# CSWrite3_0_1_V0_51.net
KiCad netlist of a schematic drawn in Altium Designer
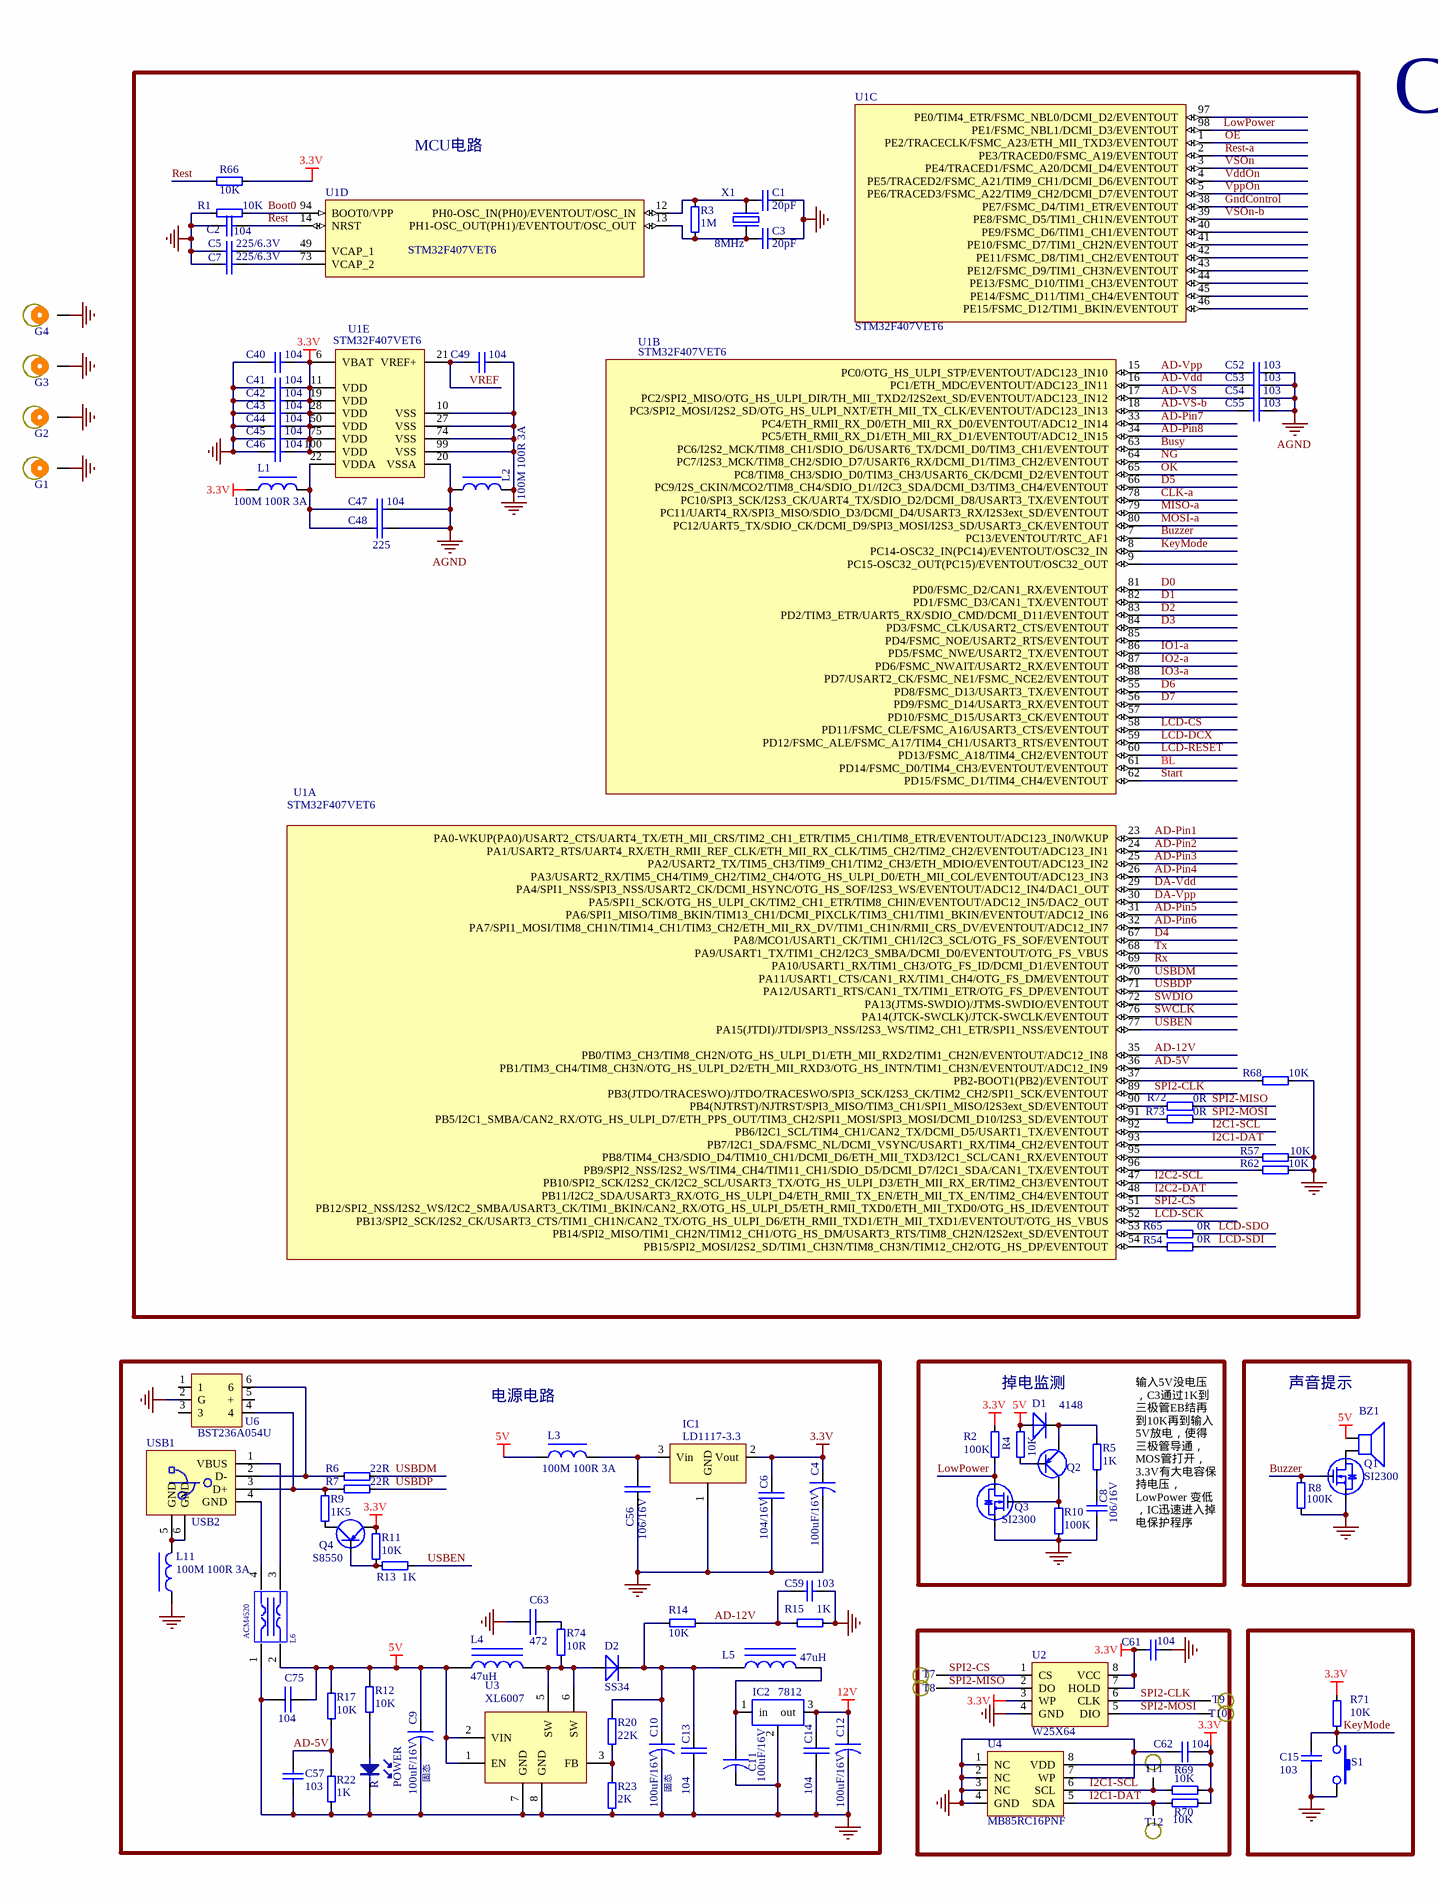
[diagram p0: CSWrite3.0.1 V0.51.SchDoc, left]
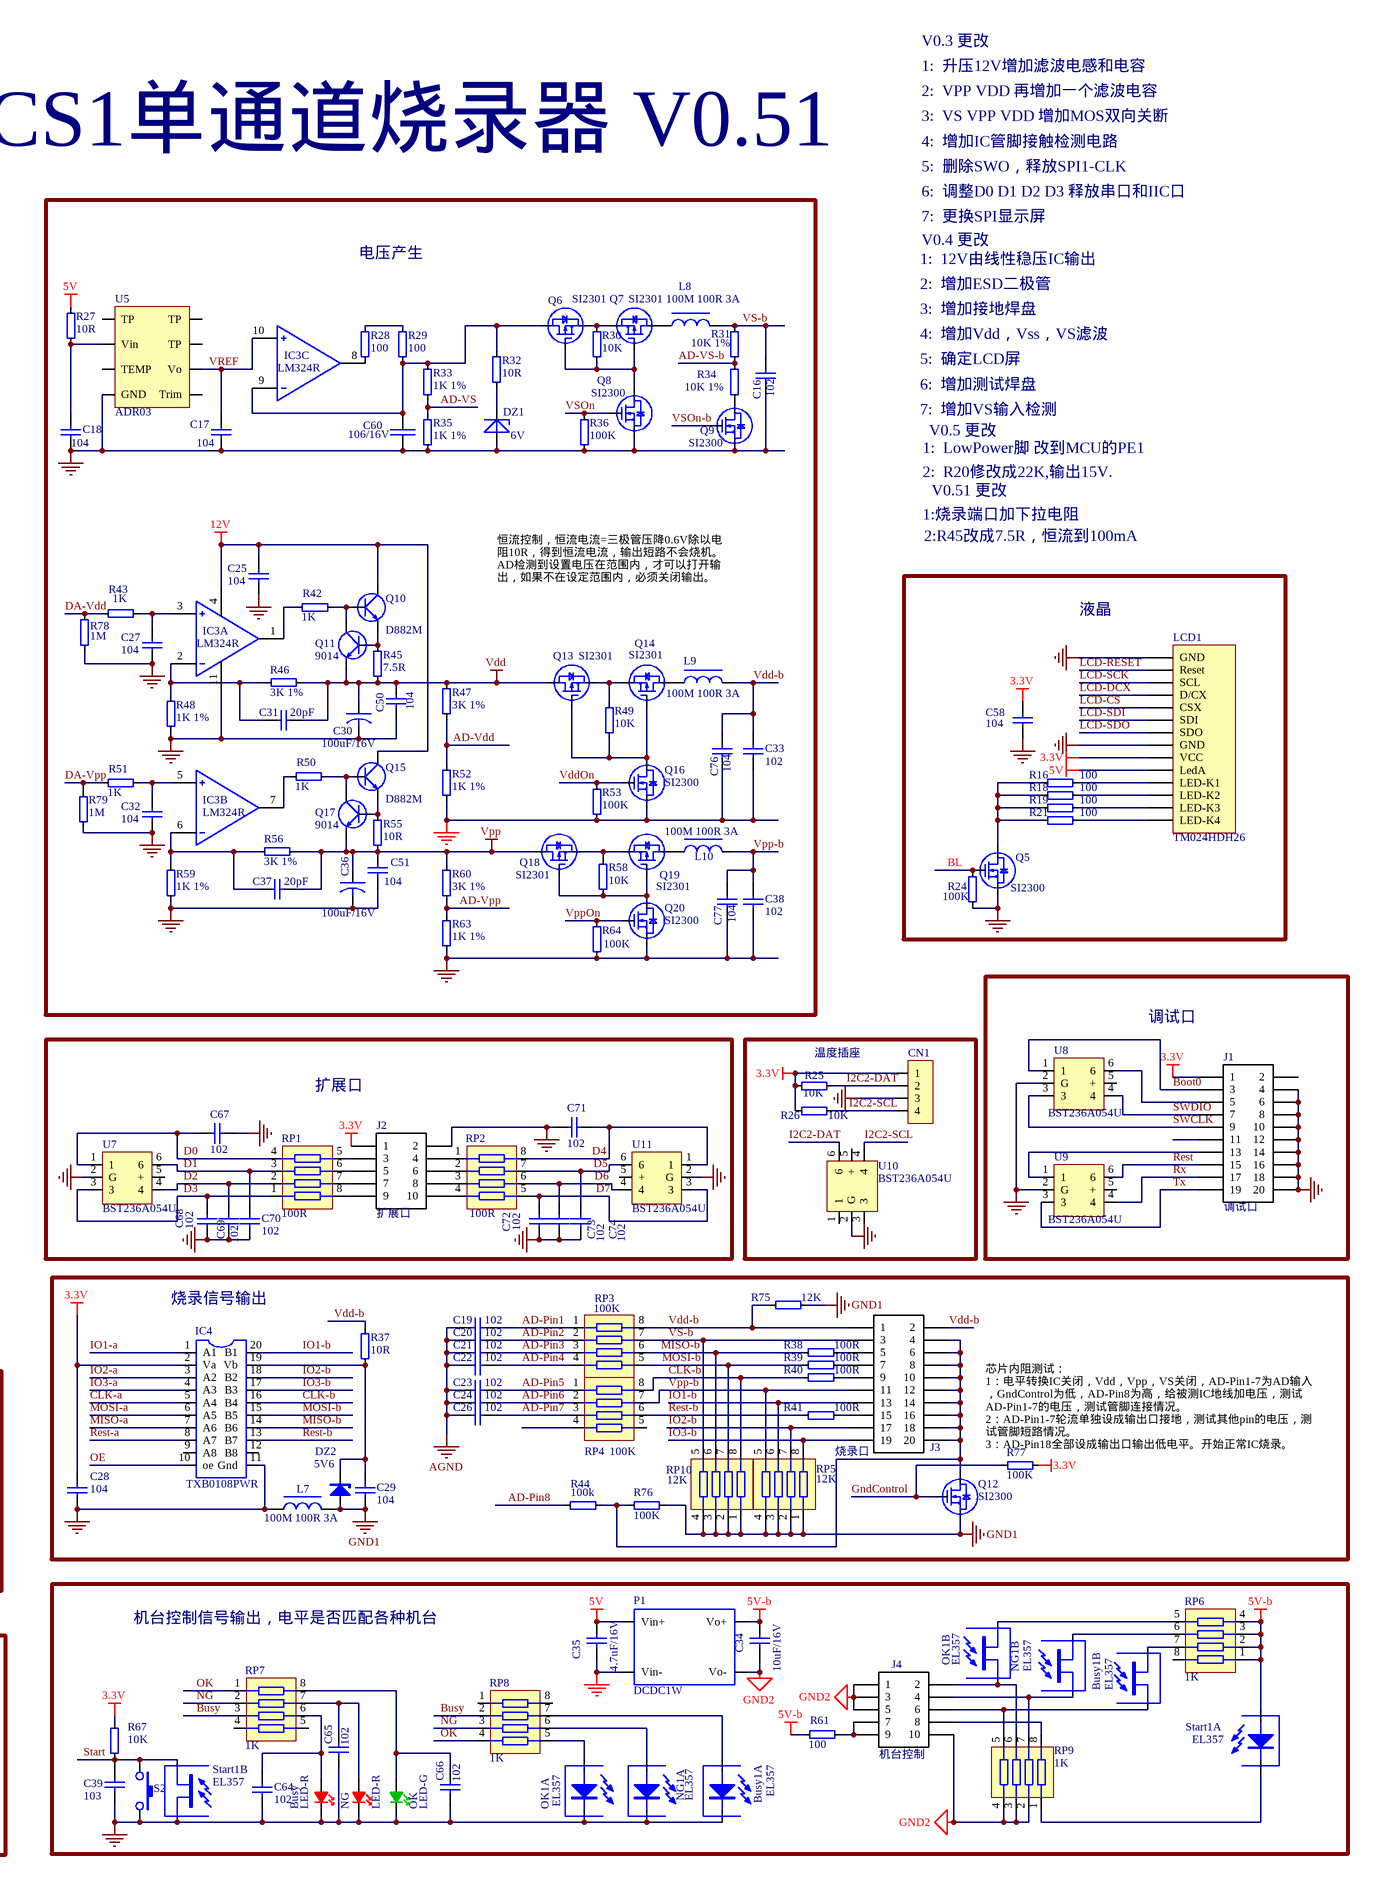
[diagram p1: CSWrite3.0.1 V0.51.SchDoc, right]

(export (version "E")
  (design (tool "Eeschema 10.0.6"))
  (components
    (comp (ref "Busy") (value "LED-R") (footprint "LED05") (libsource (lib "DCRL_W") (part "LEDR")))
    (comp (ref "Busy1") (value "EL357") (footprint "SOP-4") (libsource (lib "ASD9084-负载 V1") (part "MOS光耦")))
    (comp (ref "BZ1") (value "BUZZER") (footprint "FMQ-9*5.5") (libsource (lib "DCRL") (part "Speaker")))
    (comp (ref "C1")
      (value "20pF")
      (footprint "0603C")
      (description "无极电容")
      (libsource (lib "DCRL") (part "CAP"))
    )
    (comp (ref "C2")
      (value "104")
      (footprint "0603C")
      (description "无极电容")
      (libsource (lib "DCRL") (part "CAP"))
    )
    (comp (ref "C3")
      (value "20pF")
      (footprint "0603C")
      (description "无极电容")
      (libsource (lib "DCRL") (part "CAP"))
    )
    (comp (ref "C4")
      (value "100uF/16V")
      (footprint "CAP-B")
      (description "Capacitor")
      (libsource (lib "DCRL") (part "CAPACITOR"))
    )
    (comp (ref "C5")
      (value "225/6.3V")
      (footprint "0603C")
      (description "无极电容")
      (libsource (lib "DCRL") (part "CAP"))
    )
    (comp (ref "C6")
      (value "104/16V")
      (footprint "0603C")
      (description "无极电容")
      (libsource (lib "*") (part "CAP"))
    )
    (comp (ref "C7")
      (value "225/6.3V")
      (footprint "0603C")
      (description "无极电容")
      (libsource (lib "DCRL") (part "CAP"))
    )
    (comp (ref "C8")
      (value "106/16V")
      (footprint "0603C")
      (description "无极电容")
      (libsource (lib "DCRL") (part "CAP"))
    )
    (comp (ref "C9")
      (value "100uF/16V")
      (footprint "CB_8*11D5")
      (description "Capacitor")
      (libsource (lib "DCRL") (part "CAPACITOR"))
    )
    (comp (ref "C10")
      (value "100uF/16V")
      (footprint "CB_8*11D5")
      (description "Capacitor")
      (libsource (lib "DCRL") (part "CAPACITOR"))
    )
    (comp (ref "C11")
      (value "100uF/16V")
      (footprint "CB_8*11D5")
      (description "Capacitor")
      (libsource (lib "DCRL") (part "CAPACITOR"))
    )
    (comp (ref "C12")
      (value "100uF/16V")
      (footprint "CB_8*11D5")
      (description "Capacitor")
      (libsource (lib "DCRL") (part "CAPACITOR"))
    )
    (comp (ref "C13")
      (value "104")
      (footprint "0603C")
      (description "无极电容")
      (libsource (lib "*") (part "CAP"))
    )
    (comp (ref "C14")
      (value "104")
      (footprint "0603C")
      (description "无极电容")
      (libsource (lib "*") (part "CAP"))
    )
    (comp (ref "C15")
      (value "103")
      (footprint "0603C")
      (description "无极电容")
      (libsource (lib "DCRL") (part "CAP"))
    )
    (comp (ref "C16")
      (value "102")
      (footprint "0603C")
      (description "无极电容")
      (libsource (lib "DCRL") (part "CAP"))
    )
    (comp (ref "C17")
      (value "104")
      (footprint "0603C")
      (description "无极电容")
      (libsource (lib "DCRL") (part "CAP"))
    )
    (comp (ref "C18")
      (value "104")
      (footprint "0603C")
      (description "无极电容")
      (libsource (lib "DCRL") (part "CAP"))
    )
    (comp (ref "C19")
      (value "102")
      (footprint "0603C")
      (description "无极电容")
      (libsource (lib "DCRL") (part "CAP"))
    )
    (comp (ref "C20")
      (value "102")
      (footprint "0603C")
      (description "无极电容")
      (libsource (lib "DCRL") (part "CAP"))
    )
    (comp (ref "C21")
      (value "102")
      (footprint "0603C")
      (description "无极电容")
      (libsource (lib "DCRL") (part "CAP"))
    )
    (comp (ref "C22")
      (value "102")
      (footprint "0603C")
      (description "无极电容")
      (libsource (lib "DCRL") (part "CAP"))
    )
    (comp (ref "C23")
      (value "102")
      (footprint "0603C")
      (description "无极电容")
      (libsource (lib "DCRL") (part "CAP"))
    )
    (comp (ref "C24")
      (value "102")
      (footprint "0603C")
      (description "无极电容")
      (libsource (lib "DCRL") (part "CAP"))
    )
    (comp (ref "C25")
      (value "104")
      (footprint "0603C")
      (description "无极电容")
      (libsource (lib "DCRL") (part "CAP"))
    )
    (comp (ref "C26")
      (value "102")
      (footprint "0603C")
      (description "无极电容")
      (libsource (lib "DCRL") (part "CAP"))
    )
    (comp (ref "C27")
      (value "104")
      (footprint "0603C")
      (description "无极电容")
      (libsource (lib "DCRL") (part "CAP"))
    )
    (comp (ref "C28")
      (value "104")
      (footprint "0603C")
      (description "无极电容")
      (libsource (lib "DCRL") (part "CAP"))
    )
    (comp (ref "C29")
      (value "104")
      (footprint "0603C")
      (description "无极电容")
      (libsource (lib "DCRL") (part "CAP"))
    )
    (comp (ref "C30")
      (value "100uF/16V")
      (footprint "CAP-B")
      (description "Capacitor")
      (libsource (lib "DCRL") (part "CAPACITOR"))
    )
    (comp (ref "C31")
      (value "20pF")
      (footprint "0603C")
      (description "无极电容")
      (libsource (lib "DCRL") (part "CAP"))
    )
    (comp (ref "C32")
      (value "104")
      (footprint "0603C")
      (description "无极电容")
      (libsource (lib "DCRL") (part "CAP"))
    )
    (comp (ref "C33")
      (value "102")
      (footprint "0603C")
      (description "无极电容")
      (libsource (lib "DCRL") (part "CAP"))
    )
    (comp (ref "C34")
      (value "10uF/16V")
      (footprint "0603C")
      (description "无极电容")
      (libsource (lib "DCRL") (part "CAP"))
    )
    (comp (ref "C35")
      (value "4.7uF/16V")
      (footprint "0603C")
      (description "无极电容")
      (libsource (lib "DCRL") (part "CAP"))
    )
    (comp (ref "C36")
      (value "100uF/16V")
      (footprint "CAP-B")
      (description "Capacitor")
      (libsource (lib "DCRL") (part "CAPACITOR"))
    )
    (comp (ref "C37")
      (value "20pF")
      (footprint "0603C")
      (description "无极电容")
      (libsource (lib "DCRL") (part "CAP"))
    )
    (comp (ref "C38")
      (value "102")
      (footprint "0603C")
      (description "无极电容")
      (libsource (lib "DCRL") (part "CAP"))
    )
    (comp (ref "C39")
      (value "103")
      (footprint "0603C")
      (description "无极电容")
      (libsource (lib "DCRL") (part "CAP"))
    )
    (comp (ref "C40")
      (value "104")
      (footprint "0603C")
      (description "无极电容")
      (libsource (lib "DCRL") (part "CAP"))
    )
    (comp (ref "C41")
      (value "104")
      (footprint "0603C")
      (description "无极电容")
      (libsource (lib "DCRL") (part "CAP"))
    )
    (comp (ref "C42")
      (value "104")
      (footprint "0603C")
      (description "无极电容")
      (libsource (lib "DCRL") (part "CAP"))
    )
    (comp (ref "C43")
      (value "104")
      (footprint "0603C")
      (description "无极电容")
      (libsource (lib "DCRL") (part "CAP"))
    )
    (comp (ref "C44")
      (value "104")
      (footprint "0603C")
      (description "无极电容")
      (libsource (lib "DCRL") (part "CAP"))
    )
    (comp (ref "C45")
      (value "104")
      (footprint "0603C")
      (description "无极电容")
      (libsource (lib "DCRL") (part "CAP"))
    )
    (comp (ref "C46")
      (value "104")
      (footprint "0603C")
      (description "无极电容")
      (libsource (lib "DCRL") (part "CAP"))
    )
    (comp (ref "C47")
      (value "104")
      (footprint "0603C")
      (description "无极电容")
      (libsource (lib "DCRL") (part "CAP"))
    )
    (comp (ref "C48")
      (value "225")
      (footprint "0603C")
      (description "无极电容")
      (libsource (lib "DCRL") (part "CAP"))
    )
    (comp (ref "C49")
      (value "104")
      (footprint "0603C")
      (description "无极电容")
      (libsource (lib "DCRL") (part "CAP"))
    )
    (comp (ref "C50")
      (value "104")
      (footprint "0603C")
      (description "无极电容")
      (libsource (lib "DCRL") (part "CAP"))
    )
    (comp (ref "C51")
      (value "104")
      (footprint "0603C")
      (description "无极电容")
      (libsource (lib "DCRL") (part "CAP"))
    )
    (comp (ref "C52")
      (value "103")
      (footprint "0603C")
      (description "无极电容")
      (libsource (lib "DCRL") (part "CAP"))
    )
    (comp (ref "C53")
      (value "103")
      (footprint "0603C")
      (description "无极电容")
      (libsource (lib "DCRL") (part "CAP"))
    )
    (comp (ref "C54")
      (value "103")
      (footprint "0603C")
      (description "无极电容")
      (libsource (lib "DCRL") (part "CAP"))
    )
    (comp (ref "C55")
      (value "103")
      (footprint "0603C")
      (description "无极电容")
      (libsource (lib "DCRL") (part "CAP"))
    )
    (comp (ref "C56")
      (value "106/16V")
      (footprint "0603C")
      (description "无极电容")
      (libsource (lib "*") (part "CAP"))
    )
    (comp (ref "C57")
      (value "103")
      (footprint "0603C")
      (description "无极电容")
      (libsource (lib "DCRL") (part "CAP"))
    )
    (comp (ref "C58")
      (value "104")
      (footprint "0603C")
      (description "无极电容")
      (libsource (lib "DCRL") (part "CAP"))
    )
    (comp (ref "C59")
      (value "103")
      (footprint "0603C")
      (description "无极电容")
      (libsource (lib "DCRL") (part "CAP"))
    )
    (comp (ref "C60")
      (value "106/16V")
      (footprint "0603C")
      (description "无极电容")
      (libsource (lib "*") (part "CAP"))
    )
    (comp (ref "C61")
      (value "104")
      (footprint "0603C")
      (description "无极电容")
      (libsource (lib "DCRL") (part "CAP"))
    )
    (comp (ref "C62")
      (value "104")
      (footprint "0603C")
      (description "无极电容")
      (libsource (lib "DCRL") (part "CAP"))
    )
    (comp (ref "C63")
      (value "472")
      (footprint "0603C")
      (description "无极电容")
      (libsource (lib "*") (part "CAP"))
    )
    (comp (ref "C64")
      (value "102")
      (footprint "0603C")
      (description "无极电容")
      (libsource (lib "DCRL") (part "CAP"))
    )
    (comp (ref "C65")
      (value "102")
      (footprint "0603C")
      (description "无极电容")
      (libsource (lib "DCRL") (part "CAP"))
    )
    (comp (ref "C66")
      (value "102")
      (footprint "0603C")
      (description "无极电容")
      (libsource (lib "DCRL") (part "CAP"))
    )
    (comp (ref "C67")
      (value "102")
      (footprint "0603C")
      (description "无极电容")
      (libsource (lib "DCRL") (part "CAP"))
    )
    (comp (ref "C68")
      (value "102")
      (footprint "0603C")
      (description "无极电容")
      (libsource (lib "DCRL") (part "CAP"))
    )
    (comp (ref "C69")
      (value "102")
      (footprint "0603C")
      (description "无极电容")
      (libsource (lib "DCRL") (part "CAP"))
    )
    (comp (ref "C70")
      (value "102")
      (footprint "0603C")
      (description "无极电容")
      (libsource (lib "DCRL") (part "CAP"))
    )
    (comp (ref "C71")
      (value "102")
      (footprint "0603C")
      (description "无极电容")
      (libsource (lib "DCRL") (part "CAP"))
    )
    (comp (ref "C72")
      (value "102")
      (footprint "0603C")
      (description "无极电容")
      (libsource (lib "DCRL") (part "CAP"))
    )
    (comp (ref "C73")
      (value "102")
      (footprint "0603C")
      (description "无极电容")
      (libsource (lib "DCRL") (part "CAP"))
    )
    (comp (ref "C74")
      (value "102")
      (footprint "0603C")
      (description "无极电容")
      (libsource (lib "DCRL") (part "CAP"))
    )
    (comp (ref "C75")
      (value "104")
      (footprint "0603C")
      (description "无极电容")
      (libsource (lib "*") (part "CAP"))
    )
    (comp (ref "C76")
      (value "104")
      (footprint "0603C")
      (description "无极电容")
      (libsource (lib "DCRL") (part "CAP"))
    )
    (comp (ref "C77")
      (value "104")
      (footprint "0603C")
      (description "无极电容")
      (libsource (lib "DCRL") (part "CAP"))
    )
    (comp (ref "CN1")
      (value "温度插座")
      (footprint "PH4AW_2D0")
      (description "接插件")
      (libsource (lib "*") (part "CON4"))
    )
    (comp (ref "D1")
      (value "4148")
      (footprint "D1206")
      (description "二极管")
      (libsource (lib "我的元件") (part "D"))
    )
    (comp (ref "D2")
      (value "SS34")
      (footprint "D-SMA")
      (description "二极管")
      (libsource (lib "我的元件") (part "D"))
    )
    (comp (ref "DZ1")
      (value "6V")
      (footprint "D1206")
      (description "贴片稳压管")
      (libsource (lib "_POWERNENSCH") (part "DZ_s"))
    )
    (comp (ref "DZ2")
      (value "5V6")
      (footprint "D1206")
      (description "稳压二极管")
      (libsource (lib "DCRL") (part "DZ"))
    )
    (comp (ref "G1") (value "GND") (footprint "P1") (libsource (lib "DCRL") (part "J1")))
    (comp (ref "G2") (value "GND") (footprint "P1") (libsource (lib "DCRL") (part "J1")))
    (comp (ref "G3") (value "GND") (footprint "P1") (libsource (lib "DCRL") (part "J1")))
    (comp (ref "G4") (value "GND") (footprint "P1") (libsource (lib "DCRL") (part "J1")))
    (comp (ref "IC1") (value "LD1117-3.3") (footprint "SOT223") (libsource (lib "IC") (part "LM1117")))
    (comp (ref "IC2")
      (value "7812")
      (footprint "TO252AA")
      (description "三端稳压")
      (libsource (lib "_POWERNENSCH") (part "7805"))
    )
    (comp (ref "IC3")
      (value "LM324R")
      (footprint "SOP14")
      (description "运放IC")
      (libsource (lib "_POWERNENSCH") (part "LM324"))
    )
    (comp (ref "IC4") (value "TXB0108PWR") (footprint "TSSOP20") (libsource (lib "多脚") (part "IC20Pin")))
    (comp (ref "J1") (value "调试口") (footprint "DC_20P_W") (libsource (lib "芯海烧录器CS1") (part "Con10x2")))
    (comp (ref "J2") (value "扩展口") (footprint "IDC10-GZ") (libsource (lib "芯海烧录器CS1") (part "Con5x2")))
    (comp (ref "J3") (value "烧录口") (footprint "IDC20") (libsource (lib "芯海烧录器CS1") (part "Con10x2")))
    (comp (ref "J4") (value "机台控制") (libsource (lib "芯海烧录器CS1") (part "Con5x2")))
    (comp (ref "L1") (value "100M 100R 3A") (footprint "0603") (libsource (lib "DCRL") (part "L1")))
    (comp (ref "L2") (value "100M 100R 3A") (footprint "0603") (libsource (lib "DCRL") (part "L1")))
    (comp (ref "L3") (value "100M 100R 3A") (footprint "0603") (libsource (lib "DCRL") (part "L1")))
    (comp (ref "L4") (value "47uH") (footprint "L-SMD6.8*6.8") (libsource (lib "*") (part "INDUCTOR IRON")))
    (comp (ref "L5") (value "47uH") (footprint "L-SMD6.8*6.8") (libsource (lib "*") (part "INDUCTOR IRON")))
    (comp (ref "L6") (value "ACM4520") (footprint "L_6*7") (libsource (lib "*") (part "ACP3225")))
    (comp (ref "L7") (value "100M 100R 3A") (footprint "0603") (libsource (lib "DCRL") (part "L1")))
    (comp (ref "L8") (value "100M 100R 3A") (footprint "0603") (libsource (lib "DCRL") (part "L1")))
    (comp (ref "L9") (value "100M 100R 3A") (footprint "0603") (libsource (lib "DCRL") (part "L1")))
    (comp (ref "L10") (value "100M 100R 3A") (footprint "0603") (libsource (lib "DCRL") (part "L1")))
    (comp (ref "L11") (value "100M 100R 3A") (footprint "0603") (libsource (lib "DCRL") (part "L1")))
    (comp (ref "LCD1")
      (value "TM024HDH26")
      (footprint "TM024HDH26-V02")
      (description "jointbar")
      (libsource (lib "CSWrite3.0.1 V0.4") (part "SIP14"))
    )
    (comp (ref "NG") (value "LED-R") (footprint "LED05") (libsource (lib "DCRL_W") (part "LEDR")))
    (comp (ref "NG1") (value "EL357") (footprint "SOP-4") (libsource (lib "ASD9084-负载 V1") (part "MOS光耦")))
    (comp (ref "OK") (value "LED-G") (footprint "LED05") (libsource (lib "DCRL_W") (part "LEDG")))
    (comp (ref "OK1") (value "EL357") (footprint "SOP-4") (libsource (lib "ASD9084-负载 V1") (part "MOS光耦")))
    (comp (ref "P1") (value "DCDC1W") (footprint "1WDC_DC-4") (libsource (lib "DCRL") (part "1WDC_DC")))
    (comp (ref "POWER") (value "R") (footprint "LED05") (libsource (lib "我的元件") (part "LED-B")))
    (comp (ref "Q1")
      (value "SI2300")
      (footprint "SOT-23")
      (description "场效应管")
      (libsource (lib "DCRL") (part "MOSFET N"))
    )
    (comp (ref "Q2")
      (value "S8550")
      (footprint "SOT-23")
      (description "三极管")
      (libsource (lib "DCRL") (part "PNP1"))
    )
    (comp (ref "Q3")
      (value "SI2300")
      (footprint "SOT-23")
      (description "场效应管")
      (libsource (lib "DCRL") (part "MOSFET N"))
    )
    (comp (ref "Q4")
      (value "S8550")
      (footprint "SOT23")
      (description "三极管")
      (libsource (lib "DCRL") (part "PNP1"))
    )
    (comp (ref "Q5")
      (value "SI2300")
      (footprint "SOT-23")
      (description "场效应管")
      (libsource (lib "DCRL") (part "MOSFET N"))
    )
    (comp (ref "Q6")
      (value "SI2301")
      (footprint "SOT23")
      (description "场效应管")
      (libsource (lib "我的元件") (part "PMOS"))
    )
    (comp (ref "Q7")
      (value "SI2301")
      (footprint "SOT23")
      (description "场效应管")
      (libsource (lib "我的元件") (part "PMOS"))
    )
    (comp (ref "Q8")
      (value "SI2300")
      (footprint "SOT-23")
      (description "场效应管")
      (libsource (lib "DCRL") (part "MOSFET N"))
    )
    (comp (ref "Q9")
      (value "SI2300")
      (footprint "SOT-23")
      (description "场效应管")
      (libsource (lib "DCRL") (part "MOSFET N"))
    )
    (comp (ref "Q10")
      (value "D882M")
      (footprint "TO252AA")
      (description "三极管")
      (libsource (lib "DCRL") (part "NPN1"))
    )
    (comp (ref "Q11")
      (value "9014")
      (footprint "SOT-23")
      (description "三极管")
      (libsource (lib "DCRL") (part "NPN1"))
    )
    (comp (ref "Q12")
      (value "SI2300")
      (footprint "SOT-23")
      (description "场效应管")
      (libsource (lib "DCRL") (part "MOSFET N"))
    )
    (comp (ref "Q13")
      (value "SI2301")
      (footprint "SOT23")
      (description "场效应管")
      (libsource (lib "我的元件") (part "PMOS"))
    )
    (comp (ref "Q14")
      (value "SI2301")
      (footprint "SOT23")
      (description "场效应管")
      (libsource (lib "我的元件") (part "PMOS"))
    )
    (comp (ref "Q15")
      (value "D882M")
      (footprint "TO252AA")
      (description "三极管")
      (libsource (lib "DCRL") (part "NPN1"))
    )
    (comp (ref "Q16")
      (value "SI2300")
      (footprint "SOT-23")
      (description "场效应管")
      (libsource (lib "DCRL") (part "MOSFET N"))
    )
    (comp (ref "Q17")
      (value "9014")
      (footprint "SOT-23")
      (description "三极管")
      (libsource (lib "DCRL") (part "NPN1"))
    )
    (comp (ref "Q18")
      (value "SI2301")
      (footprint "SOT23")
      (description "场效应管")
      (libsource (lib "我的元件") (part "PMOS"))
    )
    (comp (ref "Q19")
      (value "SI2301")
      (footprint "SOT23")
      (description "场效应管")
      (libsource (lib "我的元件") (part "PMOS"))
    )
    (comp (ref "Q20")
      (value "SI2300")
      (footprint "SOT-23")
      (description "场效应管")
      (libsource (lib "DCRL") (part "MOSFET N"))
    )
    (comp (ref "R1") (value "10K") (footprint "0603") (description "电阻") (libsource (lib "DCRL") (part "R")))
    (comp (ref "R2") (value "100K") (footprint "0603") (description "电阻") (libsource (lib "DCRL") (part "R")))
    (comp (ref "R3") (value "1M") (footprint "0603") (description "电阻") (libsource (lib "DCRL") (part "R")))
    (comp (ref "R4") (value "10K") (footprint "0603") (description "电阻") (libsource (lib "DCRL") (part "R")))
    (comp (ref "R5") (value "1K") (footprint "0603") (description "电阻") (libsource (lib "DCRL") (part "R")))
    (comp (ref "R6") (value "22R") (footprint "0603") (description "电阻") (libsource (lib "DCRL") (part "R")))
    (comp (ref "R7") (value "22R") (footprint "0603") (description "电阻") (libsource (lib "DCRL") (part "R")))
    (comp (ref "R8") (value "100K") (footprint "0603") (description "电阻") (libsource (lib "DCRL") (part "R")))
    (comp (ref "R9") (value "1K5") (footprint "0603") (description "电阻") (libsource (lib "DCRL") (part "R")))
    (comp (ref "R10")
      (value "100K")
      (footprint "0603")
      (description "电阻")
      (libsource (lib "DCRL") (part "R"))
    )
    (comp (ref "R11") (value "10K") (footprint "0603") (description "电阻") (libsource (lib "DCRL") (part "R")))
    (comp (ref "R12") (value "10K") (footprint "0603") (description "电阻") (libsource (lib "DCRL") (part "R")))
    (comp (ref "R13") (value "1K") (footprint "0603") (description "电阻") (libsource (lib "DCRL") (part "R")))
    (comp (ref "R14") (value "10K") (footprint "0603") (description "电阻") (libsource (lib "DCRL") (part "R")))
    (comp (ref "R15") (value "1K") (footprint "0603") (description "电阻") (libsource (lib "DCRL") (part "R")))
    (comp (ref "R16") (value "100") (footprint "0603") (description "电阻") (libsource (lib "DCRL") (part "R")))
    (comp (ref "R17") (value "10K") (footprint "0603") (description "电阻") (libsource (lib "DCRL") (part "R")))
    (comp (ref "R18") (value "100") (footprint "0603") (description "电阻") (libsource (lib "DCRL") (part "R")))
    (comp (ref "R19") (value "100") (footprint "0603") (description "电阻") (libsource (lib "DCRL") (part "R")))
    (comp (ref "R20") (value "22K") (footprint "0603") (description "电阻") (libsource (lib "*") (part "RES")))
    (comp (ref "R21") (value "100") (footprint "0603") (description "电阻") (libsource (lib "DCRL") (part "R")))
    (comp (ref "R22") (value "1K") (footprint "0603") (description "电阻") (libsource (lib "DCRL") (part "R")))
    (comp (ref "R23") (value "2K") (footprint "0603") (description "电阻") (libsource (lib "*") (part "RES")))
    (comp (ref "R24")
      (value "100K")
      (footprint "0603")
      (description "电阻")
      (libsource (lib "DCRL") (part "R"))
    )
    (comp (ref "R25") (value "10K") (footprint "0603") (description "电阻") (libsource (lib "DCRL") (part "R")))
    (comp (ref "R26") (value "10K") (footprint "0603") (description "电阻") (libsource (lib "DCRL") (part "R")))
    (comp (ref "R27") (value "10R") (footprint "0603") (description "电阻") (libsource (lib "DCRL") (part "R")))
    (comp (ref "R28") (value "100") (footprint "0603") (description "电阻") (libsource (lib "DCRL") (part "R")))
    (comp (ref "R29") (value "100") (footprint "0603") (description "电阻") (libsource (lib "DCRL") (part "R")))
    (comp (ref "R30") (value "10K") (footprint "0603") (description "电阻") (libsource (lib "DCRL") (part "R")))
    (comp (ref "R31")
      (value "10K 1%")
      (footprint "0603")
      (description "电阻")
      (libsource (lib "DCRL") (part "R"))
    )
    (comp (ref "R32") (value "10R") (footprint "0603") (description "电阻") (libsource (lib "DCRL") (part "R")))
    (comp (ref "R33")
      (value "1K 1%")
      (footprint "0603")
      (description "电阻")
      (libsource (lib "DCRL") (part "R"))
    )
    (comp (ref "R34")
      (value "10K 1%")
      (footprint "0603")
      (description "电阻")
      (libsource (lib "DCRL") (part "R"))
    )
    (comp (ref "R35")
      (value "1K 1%")
      (footprint "0603")
      (description "电阻")
      (libsource (lib "DCRL") (part "R"))
    )
    (comp (ref "R36")
      (value "100K")
      (footprint "0603")
      (description "电阻")
      (libsource (lib "DCRL") (part "R"))
    )
    (comp (ref "R37") (value "10R") (footprint "0603") (description "电阻") (libsource (lib "DCRL") (part "R")))
    (comp (ref "R38")
      (value "100R")
      (footprint "0603")
      (description "电阻")
      (libsource (lib "DCRL") (part "R"))
    )
    (comp (ref "R39")
      (value "100R")
      (footprint "0603")
      (description "电阻")
      (libsource (lib "DCRL") (part "R"))
    )
    (comp (ref "R40")
      (value "100R")
      (footprint "0603")
      (description "电阻")
      (libsource (lib "DCRL") (part "R"))
    )
    (comp (ref "R41")
      (value "100R")
      (footprint "0603")
      (description "电阻")
      (libsource (lib "DCRL") (part "R"))
    )
    (comp (ref "R42") (value "1K") (footprint "0603") (description "电阻") (libsource (lib "DCRL") (part "R")))
    (comp (ref "R43") (value "1K") (footprint "0603") (description "电阻") (libsource (lib "DCRL") (part "R")))
    (comp (ref "R44")
      (value "100k")
      (footprint "0603")
      (description "电阻")
      (libsource (lib "DCRL") (part "R"))
    )
    (comp (ref "R45")
      (value "7.5R")
      (footprint "0603")
      (description "电阻")
      (libsource (lib "DCRL") (part "R"))
    )
    (comp (ref "R46")
      (value "3K 1%")
      (footprint "0603")
      (description "电阻")
      (libsource (lib "DCRL") (part "R"))
    )
    (comp (ref "R47")
      (value "3K 1%")
      (footprint "0603")
      (description "电阻")
      (libsource (lib "DCRL") (part "R"))
    )
    (comp (ref "R48")
      (value "1K 1%")
      (footprint "0603")
      (description "电阻")
      (libsource (lib "DCRL") (part "R"))
    )
    (comp (ref "R49") (value "10K") (footprint "0603") (description "电阻") (libsource (lib "DCRL") (part "R")))
    (comp (ref "R50") (value "1K") (footprint "0603") (description "电阻") (libsource (lib "DCRL") (part "R")))
    (comp (ref "R51") (value "1K") (footprint "0603") (description "电阻") (libsource (lib "DCRL") (part "R")))
    (comp (ref "R52")
      (value "1K 1%")
      (footprint "0603")
      (description "电阻")
      (libsource (lib "DCRL") (part "R"))
    )
    (comp (ref "R53")
      (value "100K")
      (footprint "0603")
      (description "电阻")
      (libsource (lib "DCRL") (part "R"))
    )
    (comp (ref "R54") (value "0R") (footprint "0603") (description "电阻") (libsource (lib "DCRL") (part "R")))
    (comp (ref "R55") (value "10R") (footprint "0603") (description "电阻") (libsource (lib "DCRL") (part "R")))
    (comp (ref "R56")
      (value "3K 1%")
      (footprint "0603")
      (description "电阻")
      (libsource (lib "DCRL") (part "R"))
    )
    (comp (ref "R57") (value "10K") (footprint "0603") (description "电阻") (libsource (lib "DCRL") (part "R")))
    (comp (ref "R58") (value "10K") (footprint "0603") (description "电阻") (libsource (lib "DCRL") (part "R")))
    (comp (ref "R59")
      (value "1K 1%")
      (footprint "0603")
      (description "电阻")
      (libsource (lib "DCRL") (part "R"))
    )
    (comp (ref "R60")
      (value "3K 1%")
      (footprint "0603")
      (description "电阻")
      (libsource (lib "DCRL") (part "R"))
    )
    (comp (ref "R61") (value "100") (footprint "1206") (description "电阻") (libsource (lib "DCRL") (part "R")))
    (comp (ref "R62") (value "10K") (footprint "0603") (description "电阻") (libsource (lib "DCRL") (part "R")))
    (comp (ref "R63")
      (value "1K 1%")
      (footprint "0603")
      (description "电阻")
      (libsource (lib "DCRL") (part "R"))
    )
    (comp (ref "R64")
      (value "100K")
      (footprint "0603")
      (description "电阻")
      (libsource (lib "DCRL") (part "R"))
    )
    (comp (ref "R65") (value "0R") (footprint "0603") (description "电阻") (libsource (lib "DCRL") (part "R")))
    (comp (ref "R66") (value "10K") (footprint "0603") (description "电阻") (libsource (lib "DCRL") (part "R")))
    (comp (ref "R67") (value "10K") (footprint "0603") (description "电阻") (libsource (lib "DCRL") (part "R")))
    (comp (ref "R68") (value "10K") (footprint "0603") (description "电阻") (libsource (lib "DCRL") (part "R")))
    (comp (ref "R69") (value "10K") (footprint "0603") (description "电阻") (libsource (lib "DCRL") (part "R")))
    (comp (ref "R70") (value "10K") (footprint "0603") (description "电阻") (libsource (lib "DCRL") (part "R")))
    (comp (ref "R71") (value "10K") (footprint "0603") (description "电阻") (libsource (lib "DCRL") (part "R")))
    (comp (ref "R72") (value "0R") (footprint "0603") (description "电阻") (libsource (lib "DCRL") (part "R")))
    (comp (ref "R73") (value "0R") (footprint "0603") (description "电阻") (libsource (lib "DCRL") (part "R")))
    (comp (ref "R74") (value "10R") (footprint "0603") (description "电阻") (libsource (lib "*") (part "RES")))
    (comp (ref "R75") (value "12K") (footprint "0603") (description "电阻") (libsource (lib "DCRL") (part "R")))
    (comp (ref "R76")
      (value "100K")
      (footprint "0603")
      (description "电阻")
      (libsource (lib "DCRL") (part "R"))
    )
    (comp (ref "R77")
      (value "100K")
      (footprint "0603")
      (description "电阻")
      (libsource (lib "DCRL") (part "R"))
    )
    (comp (ref "R78") (value "1M") (footprint "0603") (description "电阻") (libsource (lib "DCRL") (part "R")))
    (comp (ref "R79") (value "1M") (footprint "0603") (description "电阻") (libsource (lib "DCRL") (part "R")))
    (comp (ref "RP1") (value "100R") (footprint "0603_RX4") (libsource (lib "") (part "RP-4_2")))
    (comp (ref "RP2") (value "100R") (footprint "0603_RX4") (libsource (lib "") (part "RP-4_1")))
    (comp (ref "RP3") (value "100K") (footprint "0603_RX4") (libsource (lib "") (part "RP-4_1")))
    (comp (ref "RP4") (value "100K") (footprint "0603_RX4") (libsource (lib "") (part "RP-4_1")))
    (comp (ref "RP5") (value "12K") (footprint "0603_RX4") (libsource (lib "") (part "RP-4_1")))
    (comp (ref "RP6") (value "1K") (footprint "0603_RX4") (libsource (lib "DCRL_W") (part "RP-4")))
    (comp (ref "RP7") (value "1K") (footprint "0603_RX4") (libsource (lib "") (part "RP-4_1")))
    (comp (ref "RP8") (value "1K") (footprint "0603_RX4") (libsource (lib "") (part "RP-4_1")))
    (comp (ref "RP9") (value "1K") (footprint "0603_RX4") (libsource (lib "") (part "RP-4_1")))
    (comp (ref "RP10") (value "12K") (footprint "0603_RX4") (libsource (lib "") (part "RP-4_1")))
    (comp (ref "S1") (value "SW-PB") (footprint "SW6*6") (libsource (lib "DCRL") (part "SW-PB")))
    (comp (ref "S2") (value "SW-PB") (footprint "SW12*17_PB86") (libsource (lib "DCRL") (part "SW-PB")))
    (comp (ref "Start1") (value "EL357") (footprint "SOP-4") (libsource (lib "ASD9084-负载 V1") (part "MOS光耦")))
    (comp (ref "T7") (value "GND") (footprint "P2") (libsource (lib "CSWrite3.0.1 V0.4") (part "J1")))
    (comp (ref "T8") (value "GND") (footprint "P2") (libsource (lib "CSWrite3.0.1 V0.4") (part "J1")))
    (comp (ref "T9") (value "GND") (footprint "P2") (libsource (lib "CSWrite3.0.1 V0.4") (part "J1")))
    (comp (ref "T10") (value "GND") (footprint "P2") (libsource (lib "CSWrite3.0.1 V0.4") (part "J1")))
    (comp (ref "T11") (value "GND") (footprint "P2") (libsource (lib "CSWrite3.0.1 V0.4") (part "J1")))
    (comp (ref "T12") (value "GND") (footprint "P2") (libsource (lib "CSWrite3.0.1 V0.4") (part "J1")))
    (comp (ref "U1")
      (value "STM32F407VET6")
      (footprint "LQFP100_V")
      (libsource (lib "STM32 F4") (part "STM32F407VET6"))
    )
    (comp (ref "U2") (value "W25X64") (footprint "SO-08M") (libsource (lib "IC") (part "W25X16")))
    (comp (ref "U3") (value "XL6007") (footprint "SO-8") (libsource (lib "12053312电源") (part "XL4007")))
    (comp (ref "U4") (value "MB85RC16PNF") (footprint "SO-08M") (libsource (lib "IC") (part "W25X16")))
    (comp (ref "U5") (value "ADR03") (footprint "SOP8") (libsource (lib "IC") (part "AD680AR")))
    (comp (ref "U6") (value "BST236A054U") (footprint "SOT-23-6L") (libsource (lib "") (part "6PIN_1")))
    (comp (ref "U7") (value "BST236A054U") (footprint "SOT-23-6L") (libsource (lib "") (part "6PIN_1")))
    (comp (ref "U8") (value "BST236A054U") (footprint "SOT-23-6L") (libsource (lib "") (part "6PIN_1")))
    (comp (ref "U9") (value "BST236A054U") (footprint "SOT-23-6L") (libsource (lib "") (part "6PIN_1")))
    (comp (ref "U10") (value "BST236A054U") (footprint "SOT-23-6L") (libsource (lib "") (part "6PIN_2")))
    (comp (ref "U11") (value "BST236A054U") (footprint "SOT-23-6L") (libsource (lib "IC") (part "6PIN")))
    (comp (ref "USB1") (value "USB2") (footprint "USB2*2") (libsource (lib "我的元件") (part "USB2")))
    (comp (ref "X1")
      (value "8MHz")
      (footprint "ATX5*3.2")
      (description "晶体振荡器")
      (libsource (lib "DCRL") (part "ATX"))
    )
  )
  (nets
    (net (code "1") (name "/AD-5V") (class "Default")
      (node (ref "C57") (pin "1") (pinfunction "1_1") (pintype "passive"))
      (node (ref "R17") (pin "2") (pinfunction "2_2") (pintype "passive"))
      (node (ref "R22") (pin "1") (pinfunction "1_1") (pintype "passive"))
      (node (ref "U1") (pin "36") (pinfunction "PB1/TIM3_CH4/TIM8_CH3N/OTG_HS_ULPI_D2/ETH_MII_RXD3/OTG_HS_INTN/TIM1_CH3N/EVENTOUT/ADC12_IN9_36") (pintype "bidirectional"))
    )
    (net (code "2") (name "/AD-12V") (class "Default")
      (node (ref "C59") (pin "1") (pinfunction "1_1") (pintype "passive"))
      (node (ref "R14") (pin "2") (pinfunction "2_2") (pintype "passive"))
      (node (ref "R15") (pin "1") (pinfunction "1_1") (pintype "passive"))
      (node (ref "U1") (pin "35") (pinfunction "PB0/TIM3_CH3/TIM8_CH2N/OTG_HS_ULPI_D1/ETH_MII_RXD2/TIM1_CH2N/EVENTOUT/ADC12_IN8_35") (pintype "bidirectional"))
    )
    (net (code "3") (name "/AD-Pin1") (class "Default")
      (node (ref "C19") (pin "2") (pinfunction "2_2") (pintype "passive"))
      (node (ref "RP3") (pin "1") (pinfunction "1_1") (pintype "passive"))
      (node (ref "U1") (pin "23") (pinfunction "PA0-WKUP(PA0)/USART2_CTS/UART4_TX/ETH_MII_CRS/TIM2_CH1_ETR/TIM5_CH1/TIM8_ETR/EVENTOUT/ADC123_IN0/WKUP_23") (pintype "bidirectional"))
    )
    (net (code "4") (name "/AD-Pin2") (class "Default")
      (node (ref "C20") (pin "2") (pinfunction "2_2") (pintype "passive"))
      (node (ref "RP3") (pin "2") (pinfunction "2_2") (pintype "passive"))
      (node (ref "U1") (pin "24") (pinfunction "PA1/USART2_RTS/UART4_RX/ETH_RMII_REF_CLK/ETH_MII_RX_CLK/TIM5_CH2/TIM2_CH2/EVENTOUT/ADC123_IN1_24") (pintype "bidirectional"))
    )
    (net (code "5") (name "/AD-Pin3") (class "Default")
      (node (ref "C21") (pin "2") (pinfunction "2_2") (pintype "passive"))
      (node (ref "RP3") (pin "3") (pinfunction "3_3") (pintype "passive"))
      (node (ref "U1") (pin "25") (pinfunction "PA2/USART2_TX/TIM5_CH3/TIM9_CH1/TIM2_CH3/ETH_MDIO/EVENTOUT/ADC123_IN2_25") (pintype "bidirectional"))
    )
    (net (code "6") (name "/AD-Pin4") (class "Default")
      (node (ref "C22") (pin "2") (pinfunction "2_2") (pintype "passive"))
      (node (ref "RP3") (pin "4") (pinfunction "4_4") (pintype "passive"))
      (node (ref "U1") (pin "26") (pinfunction "PA3/USART2_RX/TIM5_CH4/TIM9_CH2/TIM2_CH4/OTG_HS_ULPI_D0/ETH_MII_COL/EVENTOUT/ADC123_IN3_26") (pintype "bidirectional"))
    )
    (net (code "7") (name "/AD-Pin5") (class "Default")
      (node (ref "C23") (pin "2") (pinfunction "2_2") (pintype "passive"))
      (node (ref "RP4") (pin "1") (pinfunction "1_1") (pintype "passive"))
      (node (ref "U1") (pin "31") (pinfunction "PA6/SPI1_MISO/TIM8_BKIN/TIM13_CH1/DCMI_PIXCLK/TIM3_CH1/TIM1_BKIN/EVENTOUT/ADC12_IN6_31") (pintype "bidirectional"))
    )
    (net (code "8") (name "/AD-Pin6") (class "Default")
      (node (ref "C24") (pin "2") (pinfunction "2_2") (pintype "passive"))
      (node (ref "RP4") (pin "2") (pinfunction "2_2") (pintype "passive"))
      (node (ref "U1") (pin "32") (pinfunction "PA7/SPI1_MOSI/TIM8_CH1N/TIM14_CH1/TIM3_CH2/ETH_MII_RX_DV/TIM1_CH1N/RMII_CRS_DV/EVENTOUT/ADC12_IN7_32") (pintype "bidirectional"))
    )
    (net (code "9") (name "/AD-Pin7") (class "Default")
      (node (ref "C26") (pin "2") (pinfunction "2_2") (pintype "passive"))
      (node (ref "RP4") (pin "3") (pinfunction "3_3") (pintype "passive"))
      (node (ref "U1") (pin "33") (pinfunction "PC4/ETH_RMII_RX_D0/ETH_MII_RX_D0/EVENTOUT/ADC12_IN14_33") (pintype "bidirectional"))
    )
    (net (code "10") (name "/AD-Pin8") (class "Default")
      (node (ref "R44") (pin "1") (pinfunction "1_1") (pintype "passive"))
      (node (ref "U1") (pin "34") (pinfunction "PC5/ETH_RMII_RX_D1/ETH_MII_RX_D1/EVENTOUT/ADC12_IN15_34") (pintype "bidirectional"))
    )
    (net (code "11") (name "/AD-VS") (class "Default")
      (node (ref "C54") (pin "2") (pinfunction "2_2") (pintype "passive"))
      (node (ref "R33") (pin "2") (pinfunction "2_2") (pintype "passive"))
      (node (ref "R35") (pin "1") (pinfunction "1_1") (pintype "passive"))
      (node (ref "U1") (pin "17") (pinfunction "PC2/SPI2_MISO/OTG_HS_ULPI_DIR/TH_MII_TXD2/I2S2ext_SD/EVENTOUT/ADC123_IN12_17") (pintype "bidirectional"))
    )
    (net (code "12") (name "/AD-VS-b") (class "Default")
      (node (ref "C55") (pin "2") (pinfunction "2_2") (pintype "passive"))
      (node (ref "R31") (pin "2") (pinfunction "2_2") (pintype "passive"))
      (node (ref "R34") (pin "1") (pinfunction "1_1") (pintype "passive"))
      (node (ref "U1") (pin "18") (pinfunction "PC3/SPI2_MOSI/I2S2_SD/OTG_HS_ULPI_NXT/ETH_MII_TX_CLK/EVENTOUT/ADC123_IN13_18") (pintype "bidirectional"))
    )
    (net (code "13") (name "/AD-Vdd") (class "Default")
      (node (ref "C53") (pin "2") (pinfunction "2_2") (pintype "passive"))
      (node (ref "R47") (pin "2") (pinfunction "2_2") (pintype "passive"))
      (node (ref "R52") (pin "1") (pinfunction "1_1") (pintype "passive"))
      (node (ref "U1") (pin "16") (pinfunction "PC1/ETH_MDC/EVENTOUT/ADC123_IN11_16") (pintype "bidirectional"))
    )
    (net (code "14") (name "/AD-Vpp") (class "Default")
      (node (ref "C52") (pin "2") (pinfunction "2_2") (pintype "passive"))
      (node (ref "R60") (pin "2") (pinfunction "2_2") (pintype "passive"))
      (node (ref "R63") (pin "1") (pinfunction "1_1") (pintype "passive"))
      (node (ref "U1") (pin "15") (pinfunction "PC0/OTG_HS_ULPI_STP/EVENTOUT/ADC123_IN10_15") (pintype "bidirectional"))
    )
    (net (code "15") (name "/BL") (class "Default")
      (node (ref "Q5") (pin "1") (pinfunction "G_1") (pintype "passive"))
      (node (ref "R24") (pin "1") (pinfunction "1_1") (pintype "passive"))
      (node (ref "U1") (pin "61") (pinfunction "PD14/FSMC_D0/TIM4_CH3/EVENTOUT/EVENTOUT_61") (pintype "bidirectional"))
    )
    (net (code "16") (name "/Boot0") (class "Default")
      (node (ref "J1") (pin "3") (pinfunction "3_3") (pintype "passive"))
      (node (ref "R1") (pin "2") (pinfunction "2_2") (pintype "passive"))
      (node (ref "U1") (pin "94") (pinfunction "BOOT0/VPP_94") (pintype "input"))
      (node (ref "U8") (pin "1") (pinfunction "1_1") (pintype "passive"))
    )
    (net (code "17") (name "/Busy") (class "Default")
      (node (ref "RP7") (pin "3") (pinfunction "3_3") (pintype "passive"))
      (node (ref "RP8") (pin "2") (pinfunction "2_2") (pintype "passive"))
      (node (ref "U1") (pin "63") (pinfunction "PC6/I2S2_MCK/TIM8_CH1/SDIO_D6/USART6_TX/DCMI_D0/TIM3_CH1/EVENTOUT_63") (pintype "bidirectional"))
    )
    (net (code "18") (name "/Buzzer") (class "Default")
      (node (ref "Q1") (pin "1") (pinfunction "G_1") (pintype "passive"))
      (node (ref "R8") (pin "1") (pinfunction "1_1") (pintype "passive"))
      (node (ref "U1") (pin "7") (pinfunction "PC13/EVENTOUT/RTC_AF1_7") (pintype "bidirectional"))
    )
    (net (code "19") (name "/CLK-a") (class "Default")
      (node (ref "IC4") (pin "5") (pinfunction "A4_5") (pintype "passive"))
      (node (ref "U1") (pin "78") (pinfunction "PC10/SPI3_SCK/I2S3_CK/UART4_TX/SDIO_D2/DCMI_D8/USART3_TX/EVENTOUT_78") (pintype "bidirectional"))
    )
    (net (code "20") (name "/CLK-b") (class "Default")
      (node (ref "IC4") (pin "16") (pinfunction "B4_16") (pintype "passive"))
      (node (ref "R40") (pin "1") (pinfunction "1_1") (pintype "passive"))
      (node (ref "RP10") (pin "8") (pinfunction "8_8") (pintype "passive"))
      (node (ref "RP4") (pin "8") (pinfunction "8_8") (pintype "passive"))
    )
    (net (code "21") (name "/D0") (class "Default")
      (node (ref "C67") (pin "2") (pinfunction "2_2") (pintype "passive"))
      (node (ref "RP1") (pin "4") (pinfunction "4_4") (pintype "passive"))
      (node (ref "U1") (pin "81") (pinfunction "PD0/FSMC_D2/CAN1_RX/EVENTOUT_81") (pintype "bidirectional"))
      (node (ref "U7") (pin "1") (pinfunction "1_1") (pintype "passive"))
    )
    (net (code "22") (name "/D1") (class "Default")
      (node (ref "C70") (pin "2") (pinfunction "2_2") (pintype "passive"))
      (node (ref "RP1") (pin "3") (pinfunction "3_3") (pintype "passive"))
      (node (ref "U1") (pin "82") (pinfunction "PD1/FSMC_D3/CAN1_TX/EVENTOUT_82") (pintype "bidirectional"))
      (node (ref "U7") (pin "6") (pinfunction "6_6") (pintype "passive"))
    )
    (net (code "23") (name "/D2") (class "Default")
      (node (ref "C69") (pin "2") (pinfunction "2_2") (pintype "passive"))
      (node (ref "RP1") (pin "2") (pinfunction "2_2") (pintype "passive"))
      (node (ref "U1") (pin "83") (pinfunction "PD2/TIM3_ETR/UART5_RX/SDIO_CMD/DCMI_D11/EVENTOUT_83") (pintype "bidirectional"))
      (node (ref "U7") (pin "4") (pinfunction "4_4") (pintype "passive"))
    )
    (net (code "24") (name "/D3") (class "Default")
      (node (ref "C68") (pin "2") (pinfunction "2_2") (pintype "passive"))
      (node (ref "RP1") (pin "1") (pinfunction "1_1") (pintype "passive"))
      (node (ref "U1") (pin "84") (pinfunction "PD3/FSMC_CLK/USART2_CTS/EVENTOUT_84") (pintype "bidirectional"))
      (node (ref "U7") (pin "3") (pinfunction "3_3") (pintype "passive"))
    )
    (net (code "25") (name "/D4") (class "Default")
      (node (ref "C71") (pin "1") (pinfunction "1_1") (pintype "passive"))
      (node (ref "RP2") (pin "8") (pinfunction "8_8") (pintype "passive"))
      (node (ref "U1") (pin "67") (pinfunction "PA8/MCO1/USART1_CK/TIM1_CH1/I2C3_SCL/OTG_FS_SOF/EVENTOUT_67") (pintype "bidirectional"))
      (node (ref "U11") (pin "1") (pinfunction "1_1") (pintype "passive"))
    )
    (net (code "26") (name "/D5") (class "Default")
      (node (ref "C74") (pin "2") (pinfunction "2_2") (pintype "passive"))
      (node (ref "RP2") (pin "7") (pinfunction "7_7") (pintype "passive"))
      (node (ref "U1") (pin "66") (pinfunction "PC9/I2S_CKIN/MCO2/TIM8_CH4/SDIO_D1//I2C3_SDA/DCMI_D3/TIM3_CH4/EVENTOUT_66") (pintype "bidirectional"))
      (node (ref "U11") (pin "6") (pinfunction "6_6") (pintype "passive"))
    )
    (net (code "27") (name "/D6") (class "Default")
      (node (ref "C73") (pin "2") (pinfunction "2_2") (pintype "passive"))
      (node (ref "RP2") (pin "6") (pinfunction "6_6") (pintype "passive"))
      (node (ref "U1") (pin "55") (pinfunction "PD8/FSMC_D13/USART3_TX/EVENTOUT_55") (pintype "bidirectional"))
      (node (ref "U11") (pin "4") (pinfunction "4_4") (pintype "passive"))
    )
    (net (code "28") (name "/D7") (class "Default")
      (node (ref "C72") (pin "2") (pinfunction "2_2") (pintype "passive"))
      (node (ref "RP2") (pin "5") (pinfunction "5_5") (pintype "passive"))
      (node (ref "U1") (pin "56") (pinfunction "PD9/FSMC_D14/USART3_RX/EVENTOUT_56") (pintype "bidirectional"))
      (node (ref "U11") (pin "3") (pinfunction "3_3") (pintype "passive"))
    )
    (net (code "29") (name "/DA-Vdd") (class "Default")
      (node (ref "R43") (pin "1") (pinfunction "1_1") (pintype "passive"))
      (node (ref "R78") (pin "2") (pinfunction "2_2") (pintype "passive"))
      (node (ref "U1") (pin "29") (pinfunction "PA4/SPI1_NSS/SPI3_NSS/USART2_CK/DCMI_HSYNC/OTG_HS_SOF/I2S3_WS/EVENTOUT/ADC12_IN4/DAC1_OUT_29") (pintype "bidirectional"))
    )
    (net (code "30") (name "/DA-Vpp") (class "Default")
      (node (ref "R51") (pin "1") (pinfunction "1_1") (pintype "passive"))
      (node (ref "R79") (pin "2") (pinfunction "2_2") (pintype "passive"))
      (node (ref "U1") (pin "30") (pinfunction "PA5/SPI1_SCK/OTG_HS_ULPI_CK/TIM2_CH1_ETR/TIM8_CHIN/EVENTOUT/ADC12_IN5/DAC2_OUT_30") (pintype "bidirectional"))
    )
    (net (code "31") (name "/GndControl") (class "Default")
      (node (ref "Q12") (pin "1") (pinfunction "G_1") (pintype "passive"))
      (node (ref "R77") (pin "2") (pinfunction "2_2") (pintype "passive"))
      (node (ref "U1") (pin "38") (pinfunction "PE7/FSMC_D4/TIM1_ETR/EVENTOUT_38") (pintype "bidirectional"))
    )
    (net (code "32") (name "/I2C1-DAT") (class "Default")
      (node (ref "R70") (pin "2") (pinfunction "2_2") (pintype "passive"))
      (node (ref "T12") (pin "1") (pinfunction "1_1") (pintype "passive"))
      (node (ref "U1") (pin "93") (pinfunction "PB7/I2C1_SDA/FSMC_NL/DCMI_VSYNC/USART1_RX/TIM4_CH2/EVENTOUT_93") (pintype "bidirectional"))
      (node (ref "U4") (pin "5") (pinfunction "DIO_5") (pintype "passive"))
    )
    (net (code "33") (name "/I2C1-SCL") (class "Default")
      (node (ref "R69") (pin "2") (pinfunction "2_2") (pintype "passive"))
      (node (ref "T11") (pin "1") (pinfunction "1_1") (pintype "passive"))
      (node (ref "U1") (pin "92") (pinfunction "PB6/I2C1_SCL/TIM4_CH1/CAN2_TX/DCMI_D5/USART1_TX/EVENTOUT_92") (pintype "bidirectional"))
      (node (ref "U4") (pin "6") (pinfunction "CLK_6") (pintype "passive"))
    )
    (net (code "34") (name "/I2C2-DAT") (class "Default")
      (node (ref "CN1") (pin "2") (pinfunction "2_2") (pintype "passive"))
      (node (ref "R25") (pin "1") (pinfunction "1_1") (pintype "passive"))
      (node (ref "U1") (pin "48") (pinfunction "PB11/I2C2_SDA/USART3_RX/OTG_HS_ULPI_D4/ETH_RMII_TX_EN/ETH_MII_TX_EN/TIM2_CH4/EVENTOUT_48") (pintype "bidirectional"))
      (node (ref "U10") (pin "6") (pinfunction "6_6") (pintype "passive"))
    )
    (net (code "35") (name "/I2C2-SCL") (class "Default")
      (node (ref "CN1") (pin "4") (pinfunction "4_4") (pintype "passive"))
      (node (ref "R26") (pin "1") (pinfunction "1_1") (pintype "passive"))
      (node (ref "U1") (pin "47") (pinfunction "PB10/SPI2_SCK/I2S2_CK/I2C2_SCL/USART3_TX/OTG_HS_ULPI_D3/ETH_MII_RX_ER/TIM2_CH3/EVENTOUT_47") (pintype "bidirectional"))
      (node (ref "U10") (pin "4") (pinfunction "4_4") (pintype "passive"))
    )
    (net (code "36") (name "/IO1-a") (class "Default")
      (node (ref "IC4") (pin "1") (pinfunction "A1_1") (pintype "passive"))
      (node (ref "U1") (pin "86") (pinfunction "PD5/FSMC_NWE/USART2_TX/EVENTOUT_86") (pintype "bidirectional"))
    )
    (net (code "37") (name "/IO1-b") (class "Default")
      (node (ref "IC4") (pin "20") (pinfunction "B1_20") (pintype "passive"))
      (node (ref "J3") (pin "13") (pinfunction "13_13") (pintype "passive"))
      (node (ref "RP5") (pin "6") (pinfunction "6_6") (pintype "passive"))
    )
    (net (code "38") (name "/IO2-a") (class "Default")
      (node (ref "IC4") (pin "3") (pinfunction "A2_3") (pintype "passive"))
      (node (ref "U1") (pin "87") (pinfunction "PD6/FSMC_NWAIT/USART2_RX/EVENTOUT_87") (pintype "bidirectional"))
    )
    (net (code "39") (name "/IO2-b") (class "Default")
      (node (ref "IC4") (pin "18") (pinfunction "B2_18") (pintype "passive"))
      (node (ref "J3") (pin "17") (pinfunction "17_17") (pintype "passive"))
      (node (ref "RP5") (pin "7") (pinfunction "7_7") (pintype "passive"))
    )
    (net (code "40") (name "/IO3-a") (class "Default")
      (node (ref "IC4") (pin "4") (pinfunction "A3_4") (pintype "passive"))
      (node (ref "U1") (pin "88") (pinfunction "PD7/USART2_CK/FSMC_NE1/FSMC_NCE2/EVENTOUT_88") (pintype "bidirectional"))
    )
    (net (code "41") (name "/IO3-b") (class "Default")
      (node (ref "IC4") (pin "17") (pinfunction "B3_17") (pintype "passive"))
      (node (ref "J3") (pin "19") (pinfunction "19_19") (pintype "passive"))
      (node (ref "RP5") (pin "8") (pinfunction "8_8") (pintype "passive"))
    )
    (net (code "42") (name "/KeyMode") (class "Default")
      (node (ref "C15") (pin "1") (pinfunction "1_1") (pintype "passive"))
      (node (ref "R71") (pin "1") (pinfunction "1_1") (pintype "passive"))
      (node (ref "S1") (pin "2") (pinfunction "2_2") (pintype "passive"))
      (node (ref "U1") (pin "8") (pinfunction "PC14-OSC32_IN(PC14)/EVENTOUT/OSC32_IN_8") (pintype "bidirectional"))
    )
    (net (code "43") (name "/LCD-CS") (class "Default")
      (node (ref "LCD1") (pin "5") (pinfunction "CSX_5") (pintype "passive"))
      (node (ref "U1") (pin "58") (pinfunction "PD11/FSMC_CLE/FSMC_A16/USART3_CTS/EVENTOUT_58") (pintype "bidirectional"))
    )
    (net (code "44") (name "/LCD-DCX") (class "Default")
      (node (ref "LCD1") (pin "4") (pinfunction "D/CX_4") (pintype "passive"))
      (node (ref "U1") (pin "59") (pinfunction "PD12/FSMC_ALE/FSMC_A17/TIM4_CH1/USART3_RTS/EVENTOUT_59") (pintype "bidirectional"))
    )
    (net (code "45") (name "/LCD-RESET") (class "Default")
      (node (ref "LCD1") (pin "2") (pinfunction "Reset_2") (pintype "passive"))
      (node (ref "U1") (pin "60") (pinfunction "PD13/FSMC_A18/TIM4_CH2/EVENTOUT_60") (pintype "bidirectional"))
    )
    (net (code "46") (name "/LCD-SCK") (class "Default")
      (node (ref "LCD1") (pin "3") (pinfunction "SCL_3") (pintype "passive"))
      (node (ref "U1") (pin "52") (pinfunction "PB13/SPI2_SCK/I2S2_CK/USART3_CTS/TIM1_CH1N/CAN2_TX/OTG_HS_ULPI_D6/ETH_RMII_TXD1/ETH_MII_TXD1/EVENTOUT/OTG_HS_VBUS_52") (pintype "bidirectional"))
    )
    (net (code "47") (name "/LCD-SDI") (class "Default")
      (node (ref "LCD1") (pin "6") (pinfunction "SDI_6") (pintype "passive"))
      (node (ref "R54") (pin "1") (pinfunction "1_1") (pintype "passive"))
    )
    (net (code "48") (name "/LCD-SDO") (class "Default")
      (node (ref "LCD1") (pin "7") (pinfunction "SDO_7") (pintype "passive"))
      (node (ref "R65") (pin "1") (pinfunction "1_1") (pintype "passive"))
    )
    (net (code "49") (name "/LowPower") (class "Default")
      (node (ref "Q3") (pin "2") (pinfunction "D_2") (pintype "passive"))
      (node (ref "R2") (pin "1") (pinfunction "1_1") (pintype "passive"))
      (node (ref "U1") (pin "98") (pinfunction "PE1/FSMC_NBL1/DCMI_D3/EVENTOUT_98") (pintype "bidirectional"))
    )
    (net (code "50") (name "/MISO-a") (class "Default")
      (node (ref "IC4") (pin "7") (pinfunction "A6_7") (pintype "passive"))
      (node (ref "U1") (pin "79") (pinfunction "PC11/UART4_RX/SPI3_MISO/SDIO_D3/DCMI_D4/USART3_RX/I2S3ext_SD/EVENTOUT_79") (pintype "bidirectional"))
    )
    (net (code "51") (name "/MISO-b") (class "Default")
      (node (ref "IC4") (pin "14") (pinfunction "B6_14") (pintype "passive"))
      (node (ref "R38") (pin "1") (pinfunction "1_1") (pintype "passive"))
      (node (ref "RP10") (pin "6") (pinfunction "6_6") (pintype "passive"))
      (node (ref "RP3") (pin "6") (pinfunction "6_6") (pintype "passive"))
    )
    (net (code "52") (name "/MOSI-a") (class "Default")
      (node (ref "IC4") (pin "6") (pinfunction "A5_6") (pintype "passive"))
      (node (ref "U1") (pin "80") (pinfunction "PC12/UART5_TX/SDIO_CK/DCMI_D9/SPI3_MOSI/I2S3_SD/USART3_CK/EVENTOUT_80") (pintype "bidirectional"))
    )
    (net (code "53") (name "/MOSI-b") (class "Default")
      (node (ref "IC4") (pin "15") (pinfunction "B5_15") (pintype "passive"))
      (node (ref "R39") (pin "1") (pinfunction "1_1") (pintype "passive"))
      (node (ref "RP10") (pin "7") (pinfunction "7_7") (pintype "passive"))
      (node (ref "RP3") (pin "5") (pinfunction "5_5") (pintype "passive"))
    )
    (net (code "54") (name "/NG") (class "Default")
      (node (ref "RP7") (pin "2") (pinfunction "2_2") (pintype "passive"))
      (node (ref "RP8") (pin "3") (pinfunction "3_3") (pintype "passive"))
      (node (ref "U1") (pin "64") (pinfunction "PC7/I2S3_MCK/TIM8_CH2/SDIO_D7/USART6_RX/DCMI_D1/TIM3_CH2/EVENTOUT_64") (pintype "bidirectional"))
    )
    (net (code "55") (name "/OE") (class "Default")
      (node (ref "IC4") (pin "10") (pinfunction "oe_10") (pintype "passive"))
      (node (ref "U1") (pin "1") (pinfunction "PE2/TRACECLK/FSMC_A23/ETH_MII_TXD3/EVENTOUT_1") (pintype "bidirectional"))
    )
    (net (code "56") (name "/OK") (class "Default")
      (node (ref "RP7") (pin "1") (pinfunction "1_1") (pintype "passive"))
      (node (ref "RP8") (pin "4") (pinfunction "4_4") (pintype "passive"))
      (node (ref "U1") (pin "65") (pinfunction "PC8/TIM8_CH3/SDIO_D0/TIM3_CH3/USART6_CK/DCMI_D2/EVENTOUT_65") (pintype "bidirectional"))
    )
    (net (code "57") (name "/Rest") (class "Default")
      (node (ref "C2") (pin "2") (pinfunction "2_2") (pintype "passive"))
      (node (ref "J1") (pin "15") (pinfunction "15_15") (pintype "passive"))
      (node (ref "R66") (pin "1") (pinfunction "1_1") (pintype "passive"))
      (node (ref "U1") (pin "14") (pinfunction "NRST_14") (pintype "bidirectional"))
      (node (ref "U9") (pin "6") (pinfunction "6_6") (pintype "passive"))
    )
    (net (code "58") (name "/Rest-a") (class "Default")
      (node (ref "IC4") (pin "8") (pinfunction "A7_8") (pintype "passive"))
      (node (ref "U1") (pin "2") (pinfunction "PE3/TRACED0/FSMC_A19/EVENTOUT_2") (pintype "bidirectional"))
    )
    (net (code "59") (name "/Rest-b") (class "Default")
      (node (ref "IC4") (pin "13") (pinfunction "B7_13") (pintype "passive"))
      (node (ref "R41") (pin "1") (pinfunction "1_1") (pintype "passive"))
      (node (ref "RP4") (pin "6") (pinfunction "6_6") (pintype "passive"))
    )
    (net (code "60") (name "/Rx") (class "Default")
      (node (ref "J1") (pin "17") (pinfunction "17_17") (pintype "passive"))
      (node (ref "U1") (pin "69") (pinfunction "PA10/USART1_RX/TIM1_CH3/OTG_FS_ID/DCMI_D1/EVENTOUT_69") (pintype "bidirectional"))
      (node (ref "U9") (pin "4") (pinfunction "4_4") (pintype "passive"))
    )
    (net (code "61") (name "/SPI2-CLK") (class "Default")
      (node (ref "T9") (pin "1") (pinfunction "1_1") (pintype "passive"))
      (node (ref "U1") (pin "89") (pinfunction "PB3(JTDO/TRACESWO)/JTDO/TRACESWO/SPI3_SCK/I2S3_CK/TIM2_CH2/SPI1_SCK/EVENTOUT_89") (pintype "bidirectional"))
      (node (ref "U2") (pin "6") (pinfunction "CLK_6") (pintype "passive"))
    )
    (net (code "62") (name "/SPI2-CS") (class "Default")
      (node (ref "T7") (pin "1") (pinfunction "1_1") (pintype "passive"))
      (node (ref "U1") (pin "51") (pinfunction "PB12/SPI2_NSS/I2S2_WS/I2C2_SMBA/USART3_CK/TIM1_BKIN/CAN2_RX/OTG_HS_ULPI_D5/ETH_RMII_TXD0/ETH_MII_TXD0/OTG_HS_ID/EVENTOUT_51") (pintype "bidirectional"))
      (node (ref "U2") (pin "1") (pinfunction "CS_1") (pintype "passive"))
    )
    (net (code "63") (name "/SPI2-MISO") (class "Default")
      (node (ref "R72") (pin "1") (pinfunction "1_1") (pintype "passive"))
      (node (ref "T8") (pin "1") (pinfunction "1_1") (pintype "passive"))
      (node (ref "U2") (pin "2") (pinfunction "DO_2") (pintype "passive"))
    )
    (net (code "64") (name "/SPI2-MOSI") (class "Default")
      (node (ref "R73") (pin "1") (pinfunction "1_1") (pintype "passive"))
      (node (ref "T10") (pin "1") (pinfunction "1_1") (pintype "passive"))
      (node (ref "U2") (pin "5") (pinfunction "DIO_5") (pintype "passive"))
    )
    (net (code "65") (name "/SWCLK") (class "Default")
      (node (ref "J1") (pin "9") (pinfunction "9_9") (pintype "passive"))
      (node (ref "U1") (pin "76") (pinfunction "PA14(JTCK-SWCLK)/JTCK-SWCLK/EVENTOUT_76") (pintype "bidirectional"))
      (node (ref "U8") (pin "3") (pinfunction "3_3") (pintype "passive"))
    )
    (net (code "66") (name "/SWDIO") (class "Default")
      (node (ref "J1") (pin "7") (pinfunction "7_7") (pintype "passive"))
      (node (ref "U1") (pin "72") (pinfunction "PA13(JTMS-SWDIO)/JTMS-SWDIO/EVENTOUT_72") (pintype "bidirectional"))
      (node (ref "U8") (pin "4") (pinfunction "4_4") (pintype "passive"))
    )
    (net (code "67") (name "/Start") (class "Default")
      (node (ref "C39") (pin "1") (pinfunction "1_1") (pintype "passive"))
      (node (ref "R67") (pin "1") (pinfunction "1_1") (pintype "passive"))
      (node (ref "S2") (pin "2") (pinfunction "2_2") (pintype "passive"))
      (node (ref "Start1") (pin "3") (pinfunction "E_3") (pintype "passive"))
      (node (ref "U1") (pin "62") (pinfunction "PD15/FSMC_D1/TIM4_CH4/EVENTOUT_62") (pintype "bidirectional"))
    )
    (net (code "68") (name "/Tx") (class "Default")
      (node (ref "J1") (pin "19") (pinfunction "19_19") (pintype "passive"))
      (node (ref "U1") (pin "68") (pinfunction "PA9/USART1_TX/TIM1_CH2/I2C3_SMBA/DCMI_D0/EVENTOUT/OTG_FS_VBUS_68") (pintype "bidirectional"))
      (node (ref "U9") (pin "3") (pinfunction "3_3") (pintype "passive"))
    )
    (net (code "69") (name "/USBDM") (class "Default")
      (node (ref "R7") (pin "1") (pinfunction "1_1") (pintype "passive"))
      (node (ref "U1") (pin "70") (pinfunction "PA11/USART1_CTS/CAN1_RX/TIM1_CH4/OTG_FS_DM/EVENTOUT_70") (pintype "bidirectional"))
    )
    (net (code "70") (name "/USBDP") (class "Default")
      (node (ref "R6") (pin "1") (pinfunction "1_1") (pintype "passive"))
      (node (ref "U1") (pin "71") (pinfunction "PA12/USART1_RTS/CAN1_TX/TIM1_ETR/OTG_FS_DP/EVENTOUT_71") (pintype "bidirectional"))
    )
    (net (code "71") (name "/USBEN") (class "Default")
      (node (ref "R13") (pin "2") (pinfunction "2_2") (pintype "passive"))
      (node (ref "U1") (pin "77") (pinfunction "PA15(JTDI)/JTDI/SPI3_NSS/I2S3_WS/TIM2_CH1_ETR/SPI1_NSS/EVENTOUT_77") (pintype "bidirectional"))
    )
    (net (code "72") (name "/VREF") (class "Default")
      (node (ref "C17") (pin "2") (pinfunction "2_2") (pintype "passive"))
      (node (ref "C49") (pin "2") (pinfunction "2_2") (pintype "passive"))
      (node (ref "IC3") (pin "10") (pinfunction "10_10") (pintype "passive"))
      (node (ref "U1") (pin "21") (pinfunction "VREF+_21") (pintype "power_in"))
      (node (ref "U5") (pin "6") (pinfunction "Vo_6") (pintype "passive"))
    )
    (net (code "73") (name "/VS-b") (class "Default")
      (node (ref "C16") (pin "1") (pinfunction "1_1") (pintype "passive"))
      (node (ref "J3") (pin "3") (pinfunction "3_3") (pintype "passive"))
      (node (ref "L8") (pin "2") (pinfunction "2_2") (pintype "passive"))
      (node (ref "R31") (pin "1") (pinfunction "1_1") (pintype "passive"))
      (node (ref "RP10") (pin "5") (pinfunction "5_5") (pintype "passive"))
      (node (ref "RP3") (pin "7") (pinfunction "7_7") (pintype "passive"))
    )
    (net (code "74") (name "/VSOn") (class "Default")
      (node (ref "Q8") (pin "1") (pinfunction "G_1") (pintype "passive"))
      (node (ref "R36") (pin "2") (pinfunction "2_2") (pintype "passive"))
      (node (ref "U1") (pin "3") (pinfunction "PE4/TRACED1/FSMC_A20/DCMI_D4/EVENTOUT_3") (pintype "bidirectional"))
    )
    (net (code "75") (name "/VSOn-b") (class "Default")
      (node (ref "Q9") (pin "1") (pinfunction "G_1") (pintype "passive"))
      (node (ref "U1") (pin "39") (pinfunction "PE8/FSMC_D5/TIM1_CH1N/EVENTOUT_39") (pintype "bidirectional"))
    )
    (net (code "76") (name "/Vdd-b") (class "Default")
      (node (ref "C33") (pin "2") (pinfunction "2_2") (pintype "passive"))
      (node (ref "C76") (pin "1") (pinfunction "1_1") (pintype "passive"))
      (node (ref "J3") (pin "1") (pinfunction "1_1") (pintype "passive"))
      (node (ref "J3") (pin "2") (pinfunction "2_2") (pintype "passive"))
      (node (ref "L9") (pin "2") (pinfunction "2_2") (pintype "passive"))
      (node (ref "R37") (pin "1") (pinfunction "1_1") (pintype "passive"))
      (node (ref "R75") (pin "1") (pinfunction "1_1") (pintype "passive"))
      (node (ref "RP3") (pin "8") (pinfunction "8_8") (pintype "passive"))
    )
    (net (code "77") (name "/VddOn") (class "Default")
      (node (ref "Q16") (pin "1") (pinfunction "G_1") (pintype "passive"))
      (node (ref "R53") (pin "2") (pinfunction "2_2") (pintype "passive"))
      (node (ref "U1") (pin "4") (pinfunction "PE5/TRACED2/FSMC_A21/TIM9_CH1/DCMI_D6/EVENTOUT_4") (pintype "bidirectional"))
    )
    (net (code "78") (name "/Vpp-b") (class "Default")
      (node (ref "C38") (pin "2") (pinfunction "2_2") (pintype "passive"))
      (node (ref "C77") (pin "1") (pinfunction "1_1") (pintype "passive"))
      (node (ref "J3") (pin "11") (pinfunction "11_11") (pintype "passive"))
      (node (ref "L10") (pin "2") (pinfunction "2_2") (pintype "passive"))
      (node (ref "RP4") (pin "7") (pinfunction "7_7") (pintype "passive"))
      (node (ref "RP5") (pin "5") (pinfunction "5_5") (pintype "passive"))
    )
    (net (code "79") (name "/VppOn") (class "Default")
      (node (ref "Q20") (pin "1") (pinfunction "G_1") (pintype "passive"))
      (node (ref "R64") (pin "2") (pinfunction "2_2") (pintype "passive"))
      (node (ref "U1") (pin "5") (pinfunction "PE6/TRACED3/FSMC_A22/TIM9_CH2/DCMI_D7/EVENTOUT_5") (pintype "bidirectional"))
    )
    (net (code "80") (name "3.3V") (class "Default")
      (node (ref "C28") (pin "1") (pinfunction "1_1") (pintype "passive"))
      (node (ref "C4") (pin "1") (pinfunction "1_1") (pintype "passive"))
      (node (ref "C40") (pin "1") (pinfunction "1_1") (pintype "passive"))
      (node (ref "C41") (pin "1") (pinfunction "1_1") (pintype "passive"))
      (node (ref "C42") (pin "1") (pinfunction "1_1") (pintype "passive"))
      (node (ref "C43") (pin "1") (pinfunction "1_1") (pintype "passive"))
      (node (ref "C44") (pin "1") (pinfunction "1_1") (pintype "passive"))
      (node (ref "C45") (pin "1") (pinfunction "1_1") (pintype "passive"))
      (node (ref "C46") (pin "1") (pinfunction "1_1") (pintype "passive"))
      (node (ref "C58") (pin "1") (pinfunction "1_1") (pintype "passive"))
      (node (ref "C6") (pin "2") (pinfunction "2_2") (pintype "passive"))
      (node (ref "C61") (pin "2") (pinfunction "2_2") (pintype "passive"))
      (node (ref "C62") (pin "1") (pinfunction "1_1") (pintype "passive"))
      (node (ref "CN1") (pin "1") (pinfunction "1_1") (pintype "passive"))
      (node (ref "IC1") (pin "2") (pinfunction "Vout_2") (pintype "passive"))
      (node (ref "IC4") (pin "2") (pinfunction "Va_2") (pintype "passive"))
      (node (ref "J1") (pin "1") (pinfunction "1_1") (pintype "passive"))
      (node (ref "J2") (pin "1") (pinfunction "1_1") (pintype "passive"))
      (node (ref "L1") (pin "1") (pinfunction "1_1") (pintype "passive"))
      (node (ref "LCD1") (pin "9") (pinfunction "VCC_9") (pintype "passive"))
      (node (ref "Q4") (pin "3") (pinfunction "E_3") (pintype "passive"))
      (node (ref "R11") (pin "1") (pinfunction "1_1") (pintype "passive"))
      (node (ref "R2") (pin "2") (pinfunction "2_2") (pintype "passive"))
      (node (ref "R25") (pin "2") (pinfunction "2_2") (pintype "passive"))
      (node (ref "R26") (pin "2") (pinfunction "2_2") (pintype "passive"))
      (node (ref "R66") (pin "2") (pinfunction "2_2") (pintype "passive"))
      (node (ref "R67") (pin "2") (pinfunction "2_2") (pintype "passive"))
      (node (ref "R69") (pin "1") (pinfunction "1_1") (pintype "passive"))
      (node (ref "R70") (pin "1") (pinfunction "1_1") (pintype "passive"))
      (node (ref "R71") (pin "2") (pinfunction "2_2") (pintype "passive"))
      (node (ref "R77") (pin "1") (pinfunction "1_1") (pintype "passive"))
      (node (ref "U1") (pin "100") (pinfunction "VDD_100") (pintype "power_in"))
      (node (ref "U1") (pin "11") (pinfunction "VDD_11") (pintype "power_in"))
      (node (ref "U1") (pin "19") (pinfunction "VDD_19") (pintype "power_in"))
      (node (ref "U1") (pin "28") (pinfunction "VDD_28") (pintype "power_in"))
      (node (ref "U1") (pin "50") (pinfunction "VDD_50") (pintype "power_in"))
      (node (ref "U1") (pin "6") (pinfunction "VBAT_6") (pintype "power_in"))
      (node (ref "U1") (pin "75") (pinfunction "VDD_75") (pintype "power_in"))
      (node (ref "U2") (pin "3") (pinfunction "WP_3") (pintype "passive"))
      (node (ref "U2") (pin "7") (pinfunction "HOLD_7") (pintype "passive"))
      (node (ref "U2") (pin "8") (pinfunction "VCC_8") (pintype "passive"))
      (node (ref "U4") (pin "8") (pinfunction "VCC_8") (pintype "passive"))
    )
    (net (code "81") (name "5V") (class "Default")
      (node (ref "BZ1") (pin "1") (pinfunction "+_1") (pintype "passive"))
      (node (ref "C35") (pin "2") (pinfunction "2_2") (pintype "passive"))
      (node (ref "C75") (pin "1") (pinfunction "1_1") (pintype "passive"))
      (node (ref "C9") (pin "1") (pinfunction "1_1") (pintype "passive"))
      (node (ref "D1") (pin "1") (pinfunction "A_1") (pintype "passive"))
      (node (ref "L3") (pin "1") (pinfunction "1_1") (pintype "passive"))
      (node (ref "L4") (pin "1") (pinfunction "1_1") (pintype "passive"))
      (node (ref "L6") (pin "2") (pinfunction "2_2") (pintype "passive"))
      (node (ref "LCD1") (pin "10") (pinfunction "LedA_10") (pintype "passive"))
      (node (ref "P1") (pin "1") (pinfunction "Vin+_1") (pintype "passive"))
      (node (ref "R12") (pin "2") (pinfunction "2_2") (pintype "passive"))
      (node (ref "R17") (pin "1") (pinfunction "1_1") (pintype "passive"))
      (node (ref "R27") (pin "2") (pinfunction "2_2") (pintype "passive"))
      (node (ref "R4") (pin "2") (pinfunction "2_2") (pintype "passive"))
      (node (ref "U3") (pin "1") (pinfunction "EN_1") (pintype "passive"))
      (node (ref "U3") (pin "2") (pinfunction "VIN_2") (pintype "passive"))
    )
    (net (code "82") (name "5V-b") (class "Default")
      (node (ref "C34") (pin "2") (pinfunction "2_2") (pintype "passive"))
      (node (ref "P1") (pin "4") (pinfunction "Vo+_4") (pintype "passive"))
      (node (ref "R61") (pin "2") (pinfunction "2_2") (pintype "passive"))
      (node (ref "RP6") (pin "1") (pinfunction "1_1") (pintype "passive"))
      (node (ref "RP6") (pin "2") (pinfunction "2_2") (pintype "passive"))
      (node (ref "RP6") (pin "3") (pinfunction "3_3") (pintype "passive"))
      (node (ref "RP6") (pin "4") (pinfunction "4_4") (pintype "passive"))
      (node (ref "Start1") (pin "1") (pinfunction "A_1") (pintype "passive"))
    )
    (net (code "83") (name "12V") (class "Default")
      (node (ref "C12") (pin "1") (pinfunction "1_1") (pintype "passive"))
      (node (ref "C14") (pin "2") (pinfunction "2_2") (pintype "passive"))
      (node (ref "C25") (pin "2") (pinfunction "2_2") (pintype "passive"))
      (node (ref "IC2") (pin "3") (pinfunction "out_3") (pintype "passive"))
      (node (ref "IC3") (pin "4") (pinfunction "4_4") (pintype "passive"))
      (node (ref "Q10") (pin "2") (pinfunction "C_2") (pintype "passive"))
      (node (ref "Q15") (pin "2") (pinfunction "C_2") (pintype "passive"))
    )
    (net (code "84") (name "AGND") (class "Default")
      (node (ref "C19") (pin "1") (pinfunction "1_1") (pintype "passive"))
      (node (ref "C20") (pin "1") (pinfunction "1_1") (pintype "passive"))
      (node (ref "C21") (pin "1") (pinfunction "1_1") (pintype "passive"))
      (node (ref "C22") (pin "1") (pinfunction "1_1") (pintype "passive"))
      (node (ref "C23") (pin "1") (pinfunction "1_1") (pintype "passive"))
      (node (ref "C24") (pin "1") (pinfunction "1_1") (pintype "passive"))
      (node (ref "C26") (pin "1") (pinfunction "1_1") (pintype "passive"))
      (node (ref "C47") (pin "2") (pinfunction "2_2") (pintype "passive"))
      (node (ref "C48") (pin "2") (pinfunction "2_2") (pintype "passive"))
      (node (ref "C52") (pin "1") (pinfunction "1_1") (pintype "passive"))
      (node (ref "C53") (pin "1") (pinfunction "1_1") (pintype "passive"))
      (node (ref "C54") (pin "1") (pinfunction "1_1") (pintype "passive"))
      (node (ref "C55") (pin "1") (pinfunction "1_1") (pintype "passive"))
      (node (ref "L2") (pin "1") (pinfunction "1_1") (pintype "passive"))
      (node (ref "U1") (pin "20") (pinfunction "VSSA_20") (pintype "power_in"))
    )
    (net (code "85") (name "GND") (class "Default")
      (node (ref "Busy") (pin "2") (pinfunction "2_2") (pintype "passive"))
      (node (ref "Busy1") (pin "2") (pinfunction "K_2") (pintype "passive"))
      (node (ref "C1") (pin "1") (pinfunction "1_1") (pintype "passive"))
      (node (ref "C10") (pin "2") (pinfunction "2_2") (pintype "passive"))
      (node (ref "C11") (pin "2") (pinfunction "2_2") (pintype "passive"))
      (node (ref "C12") (pin "2") (pinfunction "2_2") (pintype "passive"))
      (node (ref "C13") (pin "1") (pinfunction "1_1") (pintype "passive"))
      (node (ref "C14") (pin "1") (pinfunction "1_1") (pintype "passive"))
      (node (ref "C15") (pin "2") (pinfunction "2_2") (pintype "passive"))
      (node (ref "C16") (pin "2") (pinfunction "2_2") (pintype "passive"))
      (node (ref "C17") (pin "1") (pinfunction "1_1") (pintype "passive"))
      (node (ref "C18") (pin "1") (pinfunction "1_1") (pintype "passive"))
      (node (ref "C2") (pin "1") (pinfunction "1_1") (pintype "passive"))
      (node (ref "C25") (pin "1") (pinfunction "1_1") (pintype "passive"))
      (node (ref "C27") (pin "1") (pinfunction "1_1") (pintype "passive"))
      (node (ref "C28") (pin "2") (pinfunction "2_2") (pintype "passive"))
      (node (ref "C3") (pin "1") (pinfunction "1_1") (pintype "passive"))
      (node (ref "C30") (pin "2") (pinfunction "2_2") (pintype "passive"))
      (node (ref "C32") (pin "1") (pinfunction "1_1") (pintype "passive"))
      (node (ref "C33") (pin "1") (pinfunction "1_1") (pintype "passive"))
      (node (ref "C35") (pin "1") (pinfunction "1_1") (pintype "passive"))
      (node (ref "C36") (pin "2") (pinfunction "2_2") (pintype "passive"))
      (node (ref "C38") (pin "1") (pinfunction "1_1") (pintype "passive"))
      (node (ref "C39") (pin "2") (pinfunction "2_2") (pintype "passive"))
      (node (ref "C4") (pin "2") (pinfunction "2_2") (pintype "passive"))
      (node (ref "C40") (pin "2") (pinfunction "2_2") (pintype "passive"))
      (node (ref "C41") (pin "2") (pinfunction "2_2") (pintype "passive"))
      (node (ref "C42") (pin "2") (pinfunction "2_2") (pintype "passive"))
      (node (ref "C43") (pin "2") (pinfunction "2_2") (pintype "passive"))
      (node (ref "C44") (pin "2") (pinfunction "2_2") (pintype "passive"))
      (node (ref "C45") (pin "2") (pinfunction "2_2") (pintype "passive"))
      (node (ref "C46") (pin "2") (pinfunction "2_2") (pintype "passive"))
      (node (ref "C49") (pin "1") (pinfunction "1_1") (pintype "passive"))
      (node (ref "C5") (pin "1") (pinfunction "1_1") (pintype "passive"))
      (node (ref "C50") (pin "1") (pinfunction "1_1") (pintype "passive"))
      (node (ref "C51") (pin "1") (pinfunction "1_1") (pintype "passive"))
      (node (ref "C56") (pin "1") (pinfunction "1_1") (pintype "passive"))
      (node (ref "C57") (pin "2") (pinfunction "2_2") (pintype "passive"))
      (node (ref "C58") (pin "2") (pinfunction "2_2") (pintype "passive"))
      (node (ref "C59") (pin "2") (pinfunction "2_2") (pintype "passive"))
      (node (ref "C6") (pin "1") (pinfunction "1_1") (pintype "passive"))
      (node (ref "C60") (pin "1") (pinfunction "1_1") (pintype "passive"))
      (node (ref "C61") (pin "1") (pinfunction "1_1") (pintype "passive"))
      (node (ref "C62") (pin "2") (pinfunction "2_2") (pintype "passive"))
      (node (ref "C63") (pin "2") (pinfunction "2_2") (pintype "passive"))
      (node (ref "C64") (pin "1") (pinfunction "1_1") (pintype "passive"))
      (node (ref "C65") (pin "1") (pinfunction "1_1") (pintype "passive"))
      (node (ref "C66") (pin "1") (pinfunction "1_1") (pintype "passive"))
      (node (ref "C67") (pin "1") (pinfunction "1_1") (pintype "passive"))
      (node (ref "C68") (pin "1") (pinfunction "1_1") (pintype "passive"))
      (node (ref "C69") (pin "1") (pinfunction "1_1") (pintype "passive"))
      (node (ref "C7") (pin "1") (pinfunction "1_1") (pintype "passive"))
      (node (ref "C70") (pin "1") (pinfunction "1_1") (pintype "passive"))
      (node (ref "C71") (pin "2") (pinfunction "2_2") (pintype "passive"))
      (node (ref "C72") (pin "1") (pinfunction "1_1") (pintype "passive"))
      (node (ref "C73") (pin "1") (pinfunction "1_1") (pintype "passive"))
      (node (ref "C74") (pin "1") (pinfunction "1_1") (pintype "passive"))
      (node (ref "C75") (pin "2") (pinfunction "2_2") (pintype "passive"))
      (node (ref "C76") (pin "2") (pinfunction "2_2") (pintype "passive"))
      (node (ref "C77") (pin "2") (pinfunction "2_2") (pintype "passive"))
      (node (ref "C8") (pin "1") (pinfunction "1_1") (pintype "passive"))
      (node (ref "C9") (pin "2") (pinfunction "2_2") (pintype "passive"))
      (node (ref "CN1") (pin "3") (pinfunction "3_3") (pintype "passive"))
      (node (ref "DZ1") (pin "1") (pinfunction "A_1") (pintype "passive"))
      (node (ref "G1") (pin "1") (pinfunction "1_1") (pintype "passive"))
      (node (ref "G2") (pin "1") (pinfunction "1_1") (pintype "passive"))
      (node (ref "G3") (pin "1") (pinfunction "1_1") (pintype "passive"))
      (node (ref "G4") (pin "1") (pinfunction "1_1") (pintype "passive"))
      (node (ref "IC1") (pin "1") (pinfunction "GND_1") (pintype "passive"))
      (node (ref "IC2") (pin "2") (pinfunction "2_2") (pintype "passive"))
      (node (ref "IC3") (pin "11") (pinfunction "11_11") (pintype "passive"))
      (node (ref "IC4") (pin "11") (pinfunction "Gnd_11") (pintype "passive"))
      (node (ref "J1") (pin "10") (pinfunction "10_10") (pintype "passive"))
      (node (ref "J1") (pin "12") (pinfunction "12_12") (pintype "passive"))
      (node (ref "J1") (pin "14") (pinfunction "14_14") (pintype "passive"))
      (node (ref "J1") (pin "16") (pinfunction "16_16") (pintype "passive"))
      (node (ref "J1") (pin "18") (pinfunction "18_18") (pintype "passive"))
      (node (ref "J1") (pin "20") (pinfunction "20_20") (pintype "passive"))
      (node (ref "J1") (pin "4") (pinfunction "4_4") (pintype "passive"))
      (node (ref "J1") (pin "6") (pinfunction "6_6") (pintype "passive"))
      (node (ref "J1") (pin "8") (pinfunction "8_8") (pintype "passive"))
      (node (ref "J2") (pin "2") (pinfunction "2_2") (pintype "passive"))
      (node (ref "L11") (pin "1") (pinfunction "1_1") (pintype "passive"))
      (node (ref "L2") (pin "2") (pinfunction "2_2") (pintype "passive"))
      (node (ref "L6") (pin "1") (pinfunction "1_1") (pintype "passive"))
      (node (ref "L7") (pin "1") (pinfunction "1_1") (pintype "passive"))
      (node (ref "LCD1") (pin "1") (pinfunction "GND_1") (pintype "passive"))
      (node (ref "LCD1") (pin "8") (pinfunction "GND_8") (pintype "passive"))
      (node (ref "NG") (pin "2") (pinfunction "2_2") (pintype "passive"))
      (node (ref "NG1") (pin "2") (pinfunction "K_2") (pintype "passive"))
      (node (ref "OK") (pin "2") (pinfunction "2_2") (pintype "passive"))
      (node (ref "OK1") (pin "2") (pinfunction "K_2") (pintype "passive"))
      (node (ref "P1") (pin "2") (pinfunction "Vin-_2") (pintype "passive"))
      (node (ref "POWER") (pin "2") (pinfunction "K_2") (pintype "passive"))
      (node (ref "Q1") (pin "3") (pinfunction "S_3") (pintype "passive"))
      (node (ref "Q16") (pin "3") (pinfunction "S_3") (pintype "passive"))
      (node (ref "Q20") (pin "3") (pinfunction "S_3") (pintype "passive"))
      (node (ref "Q3") (pin "3") (pinfunction "S_3") (pintype "passive"))
      (node (ref "Q5") (pin "3") (pinfunction "S_3") (pintype "passive"))
      (node (ref "Q8") (pin "3") (pinfunction "S_3") (pintype "passive"))
      (node (ref "Q9") (pin "3") (pinfunction "S_3") (pintype "passive"))
      (node (ref "R1") (pin "1") (pinfunction "1_1") (pintype "passive"))
      (node (ref "R10") (pin "1") (pinfunction "1_1") (pintype "passive"))
      (node (ref "R15") (pin "2") (pinfunction "2_2") (pintype "passive"))
      (node (ref "R22") (pin "2") (pinfunction "2_2") (pintype "passive"))
      (node (ref "R23") (pin "2") (pinfunction "2_2") (pintype "passive"))
      (node (ref "R24") (pin "2") (pinfunction "2_2") (pintype "passive"))
      (node (ref "R35") (pin "2") (pinfunction "2_2") (pintype "passive"))
      (node (ref "R36") (pin "1") (pinfunction "1_1") (pintype "passive"))
      (node (ref "R48") (pin "1") (pinfunction "1_1") (pintype "passive"))
      (node (ref "R52") (pin "2") (pinfunction "2_2") (pintype "passive"))
      (node (ref "R53") (pin "1") (pinfunction "1_1") (pintype "passive"))
      (node (ref "R57") (pin "1") (pinfunction "1_1") (pintype "passive"))
      (node (ref "R59") (pin "1") (pinfunction "1_1") (pintype "passive"))
      (node (ref "R62") (pin "1") (pinfunction "1_1") (pintype "passive"))
      (node (ref "R63") (pin "2") (pinfunction "2_2") (pintype "passive"))
      (node (ref "R64") (pin "1") (pinfunction "1_1") (pintype "passive"))
      (node (ref "R68") (pin "1") (pinfunction "1_1") (pintype "passive"))
      (node (ref "R78") (pin "1") (pinfunction "1_1") (pintype "passive"))
      (node (ref "R79") (pin "1") (pinfunction "1_1") (pintype "passive"))
      (node (ref "R8") (pin "2") (pinfunction "2_2") (pintype "passive"))
      (node (ref "S1") (pin "1") (pinfunction "1_1") (pintype "passive"))
      (node (ref "S2") (pin "1") (pinfunction "1_1") (pintype "passive"))
      (node (ref "Start1") (pin "4") (pinfunction "C_4") (pintype "passive"))
      (node (ref "U1") (pin "10") (pinfunction "VSS_10") (pintype "power_in"))
      (node (ref "U1") (pin "27") (pinfunction "VSS_27") (pintype "power_in"))
      (node (ref "U1") (pin "74") (pinfunction "VSS_74") (pintype "power_in"))
      (node (ref "U1") (pin "99") (pinfunction "VSS_99") (pintype "power_in"))
      (node (ref "U10") (pin "2") (pinfunction "G_2") (pintype "passive"))
      (node (ref "U11") (pin "2") (pinfunction "G_2") (pintype "passive"))
      (node (ref "U2") (pin "4") (pinfunction "GND_4") (pintype "passive"))
      (node (ref "U3") (pin "7") (pinfunction "GND_7") (pintype "passive"))
      (node (ref "U3") (pin "8") (pinfunction "GND_8") (pintype "passive"))
      (node (ref "U4") (pin "1") (pinfunction "CS_1") (pintype "passive"))
      (node (ref "U4") (pin "2") (pinfunction "DO_2") (pintype "passive"))
      (node (ref "U4") (pin "3") (pinfunction "WP_3") (pintype "passive"))
      (node (ref "U4") (pin "4") (pinfunction "GND_4") (pintype "passive"))
      (node (ref "U4") (pin "7") (pinfunction "HOLD_7") (pintype "passive"))
      (node (ref "U5") (pin "4") (pinfunction "GND_4") (pintype "passive"))
      (node (ref "U6") (pin "2") (pinfunction "G_2") (pintype "passive"))
      (node (ref "U7") (pin "2") (pinfunction "G_2") (pintype "passive"))
      (node (ref "U8") (pin "2") (pinfunction "G_2") (pintype "passive"))
      (node (ref "U9") (pin "2") (pinfunction "G_2") (pintype "passive"))
    )
    (net (code "86") (name "GND1") (class "Default")
      (node (ref "C29") (pin "2") (pinfunction "2_2") (pintype "passive"))
      (node (ref "DZ2") (pin "1") (pinfunction "A_1") (pintype "passive"))
      (node (ref "L7") (pin "2") (pinfunction "2_2") (pintype "passive"))
      (node (ref "Q12") (pin "3") (pinfunction "S_3") (pintype "passive"))
      (node (ref "R75") (pin "2") (pinfunction "2_2") (pintype "passive"))
      (node (ref "R76") (pin "1") (pinfunction "1_1") (pintype "passive"))
      (node (ref "RP10") (pin "1") (pinfunction "1_1") (pintype "passive"))
      (node (ref "RP10") (pin "2") (pinfunction "2_2") (pintype "passive"))
      (node (ref "RP10") (pin "3") (pinfunction "3_3") (pintype "passive"))
      (node (ref "RP10") (pin "4") (pinfunction "4_4") (pintype "passive"))
      (node (ref "RP5") (pin "1") (pinfunction "1_1") (pintype "passive"))
      (node (ref "RP5") (pin "2") (pinfunction "2_2") (pintype "passive"))
      (node (ref "RP5") (pin "3") (pinfunction "3_3") (pintype "passive"))
      (node (ref "RP5") (pin "4") (pinfunction "4_4") (pintype "passive"))
    )
    (net (code "87") (name "GND2") (class "Default")
      (node (ref "C34") (pin "1") (pinfunction "1_1") (pintype "passive"))
      (node (ref "J4") (pin "1") (pinfunction "1_1") (pintype "passive"))
      (node (ref "J4") (pin "10") (pinfunction "10_10") (pintype "passive"))
      (node (ref "J4") (pin "3") (pinfunction "3_3") (pintype "passive"))
      (node (ref "J4") (pin "5") (pinfunction "5_5") (pintype "passive"))
      (node (ref "P1") (pin "3") (pinfunction "Vo-_3") (pintype "passive"))
      (node (ref "RP9") (pin "2") (pinfunction "2_2") (pintype "passive"))
      (node (ref "RP9") (pin "3") (pinfunction "3_3") (pintype "passive"))
      (node (ref "RP9") (pin "4") (pinfunction "4_4") (pintype "passive"))
    )
    (net (code "88") (name "Net-(BZ1--)") (class "Default")
      (node (ref "BZ1") (pin "2") (pinfunction "-_2") (pintype "passive"))
      (node (ref "Q1") (pin "2") (pinfunction "D_2") (pintype "passive"))
    )
    (net (code "89") (name "Net-(Busy-Pad1)") (class "Default")
      (node (ref "Busy") (pin "1") (pinfunction "1_1") (pintype "passive"))
      (node (ref "C64") (pin "2") (pinfunction "2_2") (pintype "passive"))
      (node (ref "RP7") (pin "6") (pinfunction "6_6") (pintype "passive"))
    )
    (net (code "90") (name "Net-(Busy1A-A)") (class "Default")
      (node (ref "Busy1") (pin "1") (pinfunction "A_1") (pintype "passive"))
      (node (ref "RP8") (pin "7") (pinfunction "7_7") (pintype "passive"))
    )
    (net (code "91") (name "Net-(Busy1B-C)") (class "Default")
      (node (ref "Busy1") (pin "4") (pinfunction "C_4") (pintype "passive"))
      (node (ref "RP6") (pin "7") (pinfunction "7_7") (pintype "passive"))
    )
    (net (code "92") (name "Net-(Busy1B-E)") (class "Default")
      (node (ref "Busy1") (pin "3") (pinfunction "E_3") (pintype "passive"))
      (node (ref "J4") (pin "6") (pinfunction "6_6") (pintype "passive"))
      (node (ref "RP9") (pin "5") (pinfunction "5_5") (pintype "passive"))
    )
    (net (code "93") (name "Net-(C8-Pad2)") (class "Default")
      (node (ref "C8") (pin "2") (pinfunction "2_2") (pintype "passive"))
      (node (ref "R5") (pin "1") (pinfunction "1_1") (pintype "passive"))
    )
    (net (code "94") (name "Net-(C27-Pad2)") (class "Default")
      (node (ref "C27") (pin "2") (pinfunction "2_2") (pintype "passive"))
      (node (ref "IC3") (pin "3") (pinfunction "3_3") (pintype "passive"))
      (node (ref "R43") (pin "2") (pinfunction "2_2") (pintype "passive"))
    )
    (net (code "95") (name "Net-(C31-Pad1)") (class "Default")
      (node (ref "C31") (pin "1") (pinfunction "1_1") (pintype "passive"))
      (node (ref "IC3") (pin "2") (pinfunction "2_2") (pintype "passive"))
      (node (ref "R46") (pin "1") (pinfunction "1_1") (pintype "passive"))
      (node (ref "R48") (pin "2") (pinfunction "2_2") (pintype "passive"))
    )
    (net (code "96") (name "Net-(C32-Pad2)") (class "Default")
      (node (ref "C32") (pin "2") (pinfunction "2_2") (pintype "passive"))
      (node (ref "IC3") (pin "5") (pinfunction "5_5") (pintype "passive"))
      (node (ref "R51") (pin "2") (pinfunction "2_2") (pintype "passive"))
    )
    (net (code "97") (name "Net-(C37-Pad1)") (class "Default")
      (node (ref "C37") (pin "1") (pinfunction "1_1") (pintype "passive"))
      (node (ref "IC3") (pin "6") (pinfunction "6_6") (pintype "passive"))
      (node (ref "R56") (pin "1") (pinfunction "1_1") (pintype "passive"))
      (node (ref "R59") (pin "2") (pinfunction "2_2") (pintype "passive"))
    )
    (net (code "98") (name "Net-(C63-Pad1)") (class "Default")
      (node (ref "C63") (pin "1") (pinfunction "1_1") (pintype "passive"))
      (node (ref "R74") (pin "1") (pinfunction "1_1") (pintype "passive"))
    )
    (net (code "99") (name "Net-(C65-Pad2)") (class "Default")
      (node (ref "C65") (pin "2") (pinfunction "2_2") (pintype "passive"))
      (node (ref "NG") (pin "1") (pinfunction "1_1") (pintype "passive"))
      (node (ref "RP7") (pin "7") (pinfunction "7_7") (pintype "passive"))
    )
    (net (code "100") (name "Net-(C66-Pad2)") (class "Default")
      (node (ref "C66") (pin "2") (pinfunction "2_2") (pintype "passive"))
      (node (ref "OK") (pin "1") (pinfunction "1_1") (pintype "passive"))
      (node (ref "RP7") (pin "8") (pinfunction "8_8") (pintype "passive"))
    )
    (net (code "101") (name "Net-(D1-K)") (class "Default")
      (node (ref "D1") (pin "2") (pinfunction "K_2") (pintype "passive"))
      (node (ref "Q2") (pin "3") (pinfunction "E_3") (pintype "passive"))
      (node (ref "R5") (pin "2") (pinfunction "2_2") (pintype "passive"))
    )
    (net (code "102") (name "Net-(D2-A)") (class "Default")
      (node (ref "D2") (pin "1") (pinfunction "A_1") (pintype "passive"))
      (node (ref "L4") (pin "2") (pinfunction "2_2") (pintype "passive"))
      (node (ref "R74") (pin "2") (pinfunction "2_2") (pintype "passive"))
      (node (ref "U3") (pin "5") (pinfunction "SW_5") (pintype "passive"))
      (node (ref "U3") (pin "6") (pinfunction "SW_6") (pintype "passive"))
    )
    (net (code "103") (name "Net-(D2-K)") (class "Default")
      (node (ref "C10") (pin "1") (pinfunction "1_1") (pintype "passive"))
      (node (ref "C13") (pin "2") (pinfunction "2_2") (pintype "passive"))
      (node (ref "D2") (pin "2") (pinfunction "K_2") (pintype "passive"))
      (node (ref "L5") (pin "1") (pinfunction "1_1") (pintype "passive"))
      (node (ref "R14") (pin "1") (pinfunction "1_1") (pintype "passive"))
      (node (ref "R20") (pin "1") (pinfunction "1_1") (pintype "passive"))
    )
    (net (code "104") (name "Net-(DZ1-K)") (class "Default")
      (node (ref "DZ1") (pin "2") (pinfunction "K_2") (pintype "passive"))
      (node (ref "R32") (pin "2") (pinfunction "2_2") (pintype "passive"))
    )
    (net (code "105") (name "Net-(DZ2-K)") (class "Default")
      (node (ref "C29") (pin "1") (pinfunction "1_1") (pintype "passive"))
      (node (ref "DZ2") (pin "2") (pinfunction "K_2") (pintype "passive"))
      (node (ref "IC4") (pin "19") (pinfunction "Vb_19") (pintype "passive"))
      (node (ref "R37") (pin "2") (pinfunction "2_2") (pintype "passive"))
    )
    (net (code "106") (name "Net-(IC1-Vin)") (class "Default")
      (node (ref "C56") (pin "2") (pinfunction "2_2") (pintype "passive"))
      (node (ref "IC1") (pin "3") (pinfunction "Vin_3") (pintype "passive"))
      (node (ref "L3") (pin "2") (pinfunction "2_2") (pintype "passive"))
    )
    (net (code "107") (name "Net-(IC2-in)") (class "Default")
      (node (ref "C11") (pin "1") (pinfunction "1_1") (pintype "passive"))
      (node (ref "IC2") (pin "1") (pinfunction "in_1") (pintype "passive"))
      (node (ref "L5") (pin "2") (pinfunction "2_2") (pintype "passive"))
    )
    (net (code "108") (name "Net-(IC3-Pad1)") (class "Default")
      (node (ref "IC3") (pin "1") (pinfunction "1_1") (pintype "passive"))
      (node (ref "R42") (pin "1") (pinfunction "1_1") (pintype "passive"))
    )
    (net (code "109") (name "Net-(IC3-Pad7)") (class "Default")
      (node (ref "IC3") (pin "7") (pinfunction "7_7") (pintype "passive"))
      (node (ref "R50") (pin "1") (pinfunction "1_1") (pintype "passive"))
    )
    (net (code "110") (name "Net-(IC3-Pad8)") (class "Default")
      (node (ref "IC3") (pin "8") (pinfunction "8_8") (pintype "passive"))
      (node (ref "R28") (pin "1") (pinfunction "1_1") (pintype "passive"))
    )
    (net (code "111") (name "Net-(J1-Pad5)") (class "Default")
      (node (ref "J1") (pin "5") (pinfunction "5_5") (pintype "passive"))
      (node (ref "U8") (pin "6") (pinfunction "6_6") (pintype "passive"))
    )
    (net (code "112") (name "Net-(J1-Pad13)") (class "Default")
      (node (ref "J1") (pin "13") (pinfunction "13_13") (pintype "passive"))
      (node (ref "U9") (pin "1") (pinfunction "1_1") (pintype "passive"))
    )
    (net (code "113") (name "Net-(J2-Pad3)") (class "Default")
      (node (ref "J2") (pin "3") (pinfunction "3_3") (pintype "passive"))
      (node (ref "RP1") (pin "5") (pinfunction "5_5") (pintype "passive"))
    )
    (net (code "114") (name "Net-(J2-Pad4)") (class "Default")
      (node (ref "J2") (pin "4") (pinfunction "4_4") (pintype "passive"))
      (node (ref "RP2") (pin "1") (pinfunction "1_1") (pintype "passive"))
    )
    (net (code "115") (name "Net-(J2-Pad5)") (class "Default")
      (node (ref "J2") (pin "5") (pinfunction "5_5") (pintype "passive"))
      (node (ref "RP1") (pin "6") (pinfunction "6_6") (pintype "passive"))
    )
    (net (code "116") (name "Net-(J2-Pad6)") (class "Default")
      (node (ref "J2") (pin "6") (pinfunction "6_6") (pintype "passive"))
      (node (ref "RP2") (pin "2") (pinfunction "2_2") (pintype "passive"))
    )
    (net (code "117") (name "Net-(J2-Pad7)") (class "Default")
      (node (ref "J2") (pin "7") (pinfunction "7_7") (pintype "passive"))
      (node (ref "RP1") (pin "7") (pinfunction "7_7") (pintype "passive"))
    )
    (net (code "118") (name "Net-(J2-Pad8)") (class "Default")
      (node (ref "J2") (pin "8") (pinfunction "8_8") (pintype "passive"))
      (node (ref "RP2") (pin "3") (pinfunction "3_3") (pintype "passive"))
    )
    (net (code "119") (name "Net-(J2-Pad9)") (class "Default")
      (node (ref "J2") (pin "9") (pinfunction "9_9") (pintype "passive"))
      (node (ref "RP1") (pin "8") (pinfunction "8_8") (pintype "passive"))
    )
    (net (code "120") (name "Net-(J2-Pad10)") (class "Default")
      (node (ref "J2") (pin "10") (pinfunction "10_10") (pintype "passive"))
      (node (ref "RP2") (pin "4") (pinfunction "4_4") (pintype "passive"))
    )
    (net (code "121") (name "Net-(J3-Pad5)") (class "Default")
      (node (ref "J3") (pin "5") (pinfunction "5_5") (pintype "passive"))
      (node (ref "R38") (pin "2") (pinfunction "2_2") (pintype "passive"))
    )
    (net (code "122") (name "Net-(J3-Pad7)") (class "Default")
      (node (ref "J3") (pin "7") (pinfunction "7_7") (pintype "passive"))
      (node (ref "R39") (pin "2") (pinfunction "2_2") (pintype "passive"))
    )
    (net (code "123") (name "Net-(J3-Pad9)") (class "Default")
      (node (ref "J3") (pin "9") (pinfunction "9_9") (pintype "passive"))
      (node (ref "R40") (pin "2") (pinfunction "2_2") (pintype "passive"))
    )
    (net (code "124") (name "Net-(J3-Pad15)") (class "Default")
      (node (ref "J3") (pin "15") (pinfunction "15_15") (pintype "passive"))
      (node (ref "R41") (pin "2") (pinfunction "2_2") (pintype "passive"))
    )
    (net (code "125") (name "Net-(J4-Pad7)") (class "Default")
      (node (ref "J4") (pin "7") (pinfunction "7_7") (pintype "passive"))
      (node (ref "J4") (pin "9") (pinfunction "9_9") (pintype "passive"))
      (node (ref "R61") (pin "1") (pinfunction "1_1") (pintype "passive"))
    )
    (net (code "126") (name "Net-(J4-Pad8)") (class "Default")
      (node (ref "J4") (pin "8") (pinfunction "8_8") (pintype "passive"))
      (node (ref "RP9") (pin "8") (pinfunction "8_8") (pintype "passive"))
    )
    (net (code "127") (name "Net-(L6-Pad4)") (class "Default")
      (node (ref "L6") (pin "4") (pinfunction "4_4") (pintype "passive"))
      (node (ref "USB1") (pin "4") (pinfunction "GND_4") (pintype "passive"))
    )
    (net (code "128") (name "Net-(L11-Pad2)") (class "Default")
      (node (ref "L11") (pin "2") (pinfunction "2_2") (pintype "passive"))
      (node (ref "USB1") (pin "5") (pinfunction "GND_5") (pintype "passive"))
      (node (ref "USB1") (pin "6") (pinfunction "GND_6") (pintype "passive"))
    )
    (net (code "129") (name "Net-(LCD1-LED-K1)") (class "Default")
      (node (ref "LCD1") (pin "11") (pinfunction "LED-K1_11") (pintype "passive"))
      (node (ref "R16") (pin "2") (pinfunction "2_2") (pintype "passive"))
    )
    (net (code "130") (name "Net-(LCD1-LED-K2)") (class "Default")
      (node (ref "LCD1") (pin "12") (pinfunction "LED-K2_12") (pintype "passive"))
      (node (ref "R18") (pin "2") (pinfunction "2_2") (pintype "passive"))
    )
    (net (code "131") (name "Net-(LCD1-LED-K3)") (class "Default")
      (node (ref "LCD1") (pin "13") (pinfunction "LED-K3_13") (pintype "passive"))
      (node (ref "R19") (pin "2") (pinfunction "2_2") (pintype "passive"))
    )
    (net (code "132") (name "Net-(LCD1-LED-K4)") (class "Default")
      (node (ref "LCD1") (pin "14") (pinfunction "LED-K4_14") (pintype "passive"))
      (node (ref "R21") (pin "2") (pinfunction "2_2") (pintype "passive"))
    )
    (net (code "133") (name "Net-(NG1A-A)") (class "Default")
      (node (ref "NG1") (pin "1") (pinfunction "A_1") (pintype "passive"))
      (node (ref "RP8") (pin "6") (pinfunction "6_6") (pintype "passive"))
    )
    (net (code "134") (name "Net-(NG1B-C)") (class "Default")
      (node (ref "NG1") (pin "4") (pinfunction "C_4") (pintype "passive"))
      (node (ref "RP6") (pin "6") (pinfunction "6_6") (pintype "passive"))
    )
    (net (code "135") (name "Net-(NG1B-E)") (class "Default")
      (node (ref "J4") (pin "4") (pinfunction "4_4") (pintype "passive"))
      (node (ref "NG1") (pin "3") (pinfunction "E_3") (pintype "passive"))
      (node (ref "RP9") (pin "7") (pinfunction "7_7") (pintype "passive"))
    )
    (net (code "136") (name "Net-(OK1A-A)") (class "Default")
      (node (ref "OK1") (pin "1") (pinfunction "A_1") (pintype "passive"))
      (node (ref "RP8") (pin "5") (pinfunction "5_5") (pintype "passive"))
    )
    (net (code "137") (name "Net-(OK1B-C)") (class "Default")
      (node (ref "OK1") (pin "4") (pinfunction "C_4") (pintype "passive"))
      (node (ref "RP6") (pin "5") (pinfunction "5_5") (pintype "passive"))
    )
    (net (code "138") (name "Net-(OK1B-E)") (class "Default")
      (node (ref "J4") (pin "2") (pinfunction "2_2") (pintype "passive"))
      (node (ref "OK1") (pin "3") (pinfunction "E_3") (pintype "passive"))
      (node (ref "RP9") (pin "6") (pinfunction "6_6") (pintype "passive"))
    )
    (net (code "139") (name "Net-(POWER-A)") (class "Default")
      (node (ref "POWER") (pin "1") (pinfunction "A_1") (pintype "passive"))
      (node (ref "R12") (pin "1") (pinfunction "1_1") (pintype "passive"))
    )
    (net (code "140") (name "Net-(Q2-B)") (class "Default")
      (node (ref "Q2") (pin "1") (pinfunction "B_1") (pintype "passive"))
      (node (ref "R4") (pin "1") (pinfunction "1_1") (pintype "passive"))
    )
    (net (code "141") (name "Net-(Q2-C)") (class "Default")
      (node (ref "Q2") (pin "2") (pinfunction "C_2") (pintype "passive"))
      (node (ref "Q3") (pin "1") (pinfunction "G_1") (pintype "passive"))
      (node (ref "R10") (pin "2") (pinfunction "2_2") (pintype "passive"))
    )
    (net (code "142") (name "Net-(Q4-B)") (class "Default")
      (node (ref "Q4") (pin "1") (pinfunction "B_1") (pintype "passive"))
      (node (ref "R11") (pin "2") (pinfunction "2_2") (pintype "passive"))
      (node (ref "R13") (pin "1") (pinfunction "1_1") (pintype "passive"))
    )
    (net (code "143") (name "Net-(Q4-C)") (class "Default")
      (node (ref "Q4") (pin "2") (pinfunction "C_2") (pintype "passive"))
      (node (ref "R9") (pin "2") (pinfunction "2_2") (pintype "passive"))
    )
    (net (code "144") (name "Net-(Q5-D)") (class "Default")
      (node (ref "Q5") (pin "2") (pinfunction "D_2") (pintype "passive"))
      (node (ref "R16") (pin "1") (pinfunction "1_1") (pintype "passive"))
      (node (ref "R18") (pin "1") (pinfunction "1_1") (pintype "passive"))
      (node (ref "R19") (pin "1") (pinfunction "1_1") (pintype "passive"))
      (node (ref "R21") (pin "1") (pinfunction "1_1") (pintype "passive"))
    )
    (net (code "145") (name "Net-(Q6-D)") (class "Default")
      (node (ref "C60") (pin "2") (pinfunction "2_2") (pintype "passive"))
      (node (ref "IC3") (pin "9") (pinfunction "9_9") (pintype "passive"))
      (node (ref "Q6") (pin "2") (pinfunction "D_2") (pintype "passive"))
      (node (ref "R29") (pin "1") (pinfunction "1_1") (pintype "passive"))
      (node (ref "R32") (pin "1") (pinfunction "1_1") (pintype "passive"))
      (node (ref "R33") (pin "1") (pinfunction "1_1") (pintype "passive"))
    )
    (net (code "146") (name "Net-(Q6-G)") (class "Default")
      (node (ref "Q6") (pin "1") (pinfunction "G_1") (pintype "passive"))
      (node (ref "Q7") (pin "1") (pinfunction "G_1") (pintype "passive"))
      (node (ref "Q8") (pin "2") (pinfunction "D_2") (pintype "passive"))
      (node (ref "R30") (pin "1") (pinfunction "1_1") (pintype "passive"))
    )
    (net (code "147") (name "Net-(Q6-S)") (class "Default")
      (node (ref "Q6") (pin "3") (pinfunction "S_3") (pintype "passive"))
      (node (ref "Q7") (pin "3") (pinfunction "S_3") (pintype "passive"))
      (node (ref "R30") (pin "2") (pinfunction "2_2") (pintype "passive"))
    )
    (net (code "148") (name "Net-(Q7-D)") (class "Default")
      (node (ref "L8") (pin "1") (pinfunction "1_1") (pintype "passive"))
      (node (ref "Q7") (pin "2") (pinfunction "D_2") (pintype "passive"))
    )
    (net (code "149") (name "Net-(Q9-D)") (class "Default")
      (node (ref "Q9") (pin "2") (pinfunction "D_2") (pintype "passive"))
      (node (ref "R34") (pin "2") (pinfunction "2_2") (pintype "passive"))
    )
    (net (code "150") (name "Net-(Q10-B)") (class "Default")
      (node (ref "Q10") (pin "1") (pinfunction "B_1") (pintype "passive"))
      (node (ref "Q11") (pin "2") (pinfunction "C_2") (pintype "passive"))
      (node (ref "R42") (pin "2") (pinfunction "2_2") (pintype "passive"))
    )
    (net (code "151") (name "Net-(Q10-E)") (class "Default")
      (node (ref "Q10") (pin "3") (pinfunction "E_3") (pintype "passive"))
      (node (ref "Q11") (pin "1") (pinfunction "B_1") (pintype "passive"))
      (node (ref "R45") (pin "1") (pinfunction "1_1") (pintype "passive"))
    )
    (net (code "152") (name "Net-(Q12-D)") (class "Default")
      (node (ref "J3") (pin "10") (pinfunction "10_10") (pintype "passive"))
      (node (ref "J3") (pin "12") (pinfunction "12_12") (pintype "passive"))
      (node (ref "J3") (pin "14") (pinfunction "14_14") (pintype "passive"))
      (node (ref "J3") (pin "16") (pinfunction "16_16") (pintype "passive"))
      (node (ref "J3") (pin "18") (pinfunction "18_18") (pintype "passive"))
      (node (ref "J3") (pin "20") (pinfunction "20_20") (pintype "passive"))
      (node (ref "J3") (pin "4") (pinfunction "4_4") (pintype "passive"))
      (node (ref "J3") (pin "6") (pinfunction "6_6") (pintype "passive"))
      (node (ref "J3") (pin "8") (pinfunction "8_8") (pintype "passive"))
      (node (ref "Q12") (pin "2") (pinfunction "D_2") (pintype "passive"))
      (node (ref "R44") (pin "2") (pinfunction "2_2") (pintype "passive"))
      (node (ref "R76") (pin "2") (pinfunction "2_2") (pintype "passive"))
    )
    (net (code "153") (name "Net-(Q13-G)") (class "Default")
      (node (ref "Q13") (pin "1") (pinfunction "G_1") (pintype "passive"))
      (node (ref "Q14") (pin "1") (pinfunction "G_1") (pintype "passive"))
      (node (ref "Q16") (pin "2") (pinfunction "D_2") (pintype "passive"))
      (node (ref "R49") (pin "1") (pinfunction "1_1") (pintype "passive"))
    )
    (net (code "154") (name "Net-(Q13-S)") (class "Default")
      (node (ref "Q13") (pin "3") (pinfunction "S_3") (pintype "passive"))
      (node (ref "Q14") (pin "3") (pinfunction "S_3") (pintype "passive"))
      (node (ref "R49") (pin "2") (pinfunction "2_2") (pintype "passive"))
    )
    (net (code "155") (name "Net-(Q14-D)") (class "Default")
      (node (ref "L9") (pin "1") (pinfunction "1_1") (pintype "passive"))
      (node (ref "Q14") (pin "2") (pinfunction "D_2") (pintype "passive"))
    )
    (net (code "156") (name "Net-(Q15-B)") (class "Default")
      (node (ref "Q15") (pin "1") (pinfunction "B_1") (pintype "passive"))
      (node (ref "Q17") (pin "2") (pinfunction "C_2") (pintype "passive"))
      (node (ref "R50") (pin "2") (pinfunction "2_2") (pintype "passive"))
    )
    (net (code "157") (name "Net-(Q15-E)") (class "Default")
      (node (ref "Q15") (pin "3") (pinfunction "E_3") (pintype "passive"))
      (node (ref "Q17") (pin "1") (pinfunction "B_1") (pintype "passive"))
      (node (ref "R55") (pin "1") (pinfunction "1_1") (pintype "passive"))
    )
    (net (code "158") (name "Net-(Q18-G)") (class "Default")
      (node (ref "Q18") (pin "1") (pinfunction "G_1") (pintype "passive"))
      (node (ref "Q19") (pin "1") (pinfunction "G_1") (pintype "passive"))
      (node (ref "Q20") (pin "2") (pinfunction "D_2") (pintype "passive"))
      (node (ref "R58") (pin "1") (pinfunction "1_1") (pintype "passive"))
    )
    (net (code "159") (name "Net-(Q18-S)") (class "Default")
      (node (ref "Q18") (pin "3") (pinfunction "S_3") (pintype "passive"))
      (node (ref "Q19") (pin "3") (pinfunction "S_3") (pintype "passive"))
      (node (ref "R58") (pin "2") (pinfunction "2_2") (pintype "passive"))
    )
    (net (code "160") (name "Net-(Q19-D)") (class "Default")
      (node (ref "L10") (pin "1") (pinfunction "1_1") (pintype "passive"))
      (node (ref "Q19") (pin "2") (pinfunction "D_2") (pintype "passive"))
    )
    (net (code "161") (name "Net-(R28-Pad2)") (class "Default")
      (node (ref "R28") (pin "2") (pinfunction "2_2") (pintype "passive"))
      (node (ref "R29") (pin "2") (pinfunction "2_2") (pintype "passive"))
    )
    (net (code "162") (name "Net-(Start1A-K)") (class "Default")
      (node (ref "RP9") (pin "1") (pinfunction "1_1") (pintype "passive"))
      (node (ref "Start1") (pin "2") (pinfunction "K_2") (pintype "passive"))
    )
    (net (code "163") (name "Net-(U1A-PB2-BOOT1(PB2){slash}EVENTOUT)") (class "Default")
      (node (ref "R68") (pin "2") (pinfunction "2_2") (pintype "passive"))
      (node (ref "U1") (pin "37") (pinfunction "PB2-BOOT1(PB2)/EVENTOUT_37") (pintype "bidirectional"))
    )
    (net (code "164") (name "Net-(U1A-PB4(NJTRST){slash}NJTRST{slash}SPI3_MISO{slash}TIM3_CH1{slash}SPI1_MISO{slash}I2S3ext_SD{slash}EVENTOUT)") (class "Default")
      (node (ref "R72") (pin "2") (pinfunction "2_2") (pintype "passive"))
      (node (ref "U1") (pin "90") (pinfunction "PB4(NJTRST)/NJTRST/SPI3_MISO/TIM3_CH1/SPI1_MISO/I2S3ext_SD/EVENTOUT_90") (pintype "bidirectional"))
    )
    (net (code "165") (name "Net-(U1A-PB5{slash}I2C1_SMBA{slash}CAN2_RX{slash}OTG_HS_ULPI_D7{slash}ETH_PPS_OUT{slash}TIM3_CH2{slash}SPI1_MOSI{slash}SPI3_MOSI{slash}DCMI_D10{slash}I2S3_SD{slash}EVENTOUT)") (class "Default")
      (node (ref "R73") (pin "2") (pinfunction "2_2") (pintype "passive"))
      (node (ref "U1") (pin "91") (pinfunction "PB5/I2C1_SMBA/CAN2_RX/OTG_HS_ULPI_D7/ETH_PPS_OUT/TIM3_CH2/SPI1_MOSI/SPI3_MOSI/DCMI_D10/I2S3_SD/EVENTOUT_91") (pintype "bidirectional"))
    )
    (net (code "166") (name "Net-(U1A-PB8{slash}TIM4_CH3{slash}SDIO_D4{slash}TIM10_CH1{slash}DCMI_D6{slash}ETH_MII_TXD3{slash}I2C1_SCL{slash}CAN1_RX{slash}EVENTOUT)") (class "Default")
      (node (ref "R57") (pin "2") (pinfunction "2_2") (pintype "passive"))
      (node (ref "U1") (pin "95") (pinfunction "PB8/TIM4_CH3/SDIO_D4/TIM10_CH1/DCMI_D6/ETH_MII_TXD3/I2C1_SCL/CAN1_RX/EVENTOUT_95") (pintype "bidirectional"))
    )
    (net (code "167") (name "Net-(U1A-PB9{slash}SPI2_NSS{slash}I2S2_WS{slash}TIM4_CH4{slash}TIM11_CH1{slash}SDIO_D5{slash}DCMI_D7{slash}I2C1_SDA{slash}CAN1_TX{slash}EVENTOUT)") (class "Default")
      (node (ref "R62") (pin "2") (pinfunction "2_2") (pintype "passive"))
      (node (ref "U1") (pin "96") (pinfunction "PB9/SPI2_NSS/I2S2_WS/TIM4_CH4/TIM11_CH1/SDIO_D5/DCMI_D7/I2C1_SDA/CAN1_TX/EVENTOUT_96") (pintype "bidirectional"))
    )
    (net (code "168") (name "Net-(U1A-PB14{slash}SPI2_MISO{slash}TIM1_CH2N{slash}TIM12_CH1{slash}OTG_HS_DM{slash}USART3_RTS{slash}TIM8_CH2N{slash}I2S2ext_SD{slash}EVENTOUT)") (class "Default")
      (node (ref "R65") (pin "2") (pinfunction "2_2") (pintype "passive"))
      (node (ref "U1") (pin "53") (pinfunction "PB14/SPI2_MISO/TIM1_CH2N/TIM12_CH1/OTG_HS_DM/USART3_RTS/TIM8_CH2N/I2S2ext_SD/EVENTOUT_53") (pintype "bidirectional"))
    )
    (net (code "169") (name "Net-(U1A-PB15{slash}SPI2_MOSI{slash}I2S2_SD{slash}TIM1_CH3N{slash}TIM8_CH3N{slash}TIM12_CH2{slash}OTG_HS_DP{slash}EVENTOUT)") (class "Default")
      (node (ref "R54") (pin "2") (pinfunction "2_2") (pintype "passive"))
      (node (ref "U1") (pin "54") (pinfunction "PB15/SPI2_MOSI/I2S2_SD/TIM1_CH3N/TIM8_CH3N/TIM12_CH2/OTG_HS_DP/EVENTOUT_54") (pintype "bidirectional"))
    )
    (net (code "170") (name "Net-(U1D-PH0-OSC_IN(PH0){slash}EVENTOUT{slash}OSC_IN)") (class "Default")
      (node (ref "C1") (pin "2") (pinfunction "2_2") (pintype "passive"))
      (node (ref "R3") (pin "2") (pinfunction "2_2") (pintype "passive"))
      (node (ref "U1") (pin "12") (pinfunction "PH0-OSC_IN(PH0)/EVENTOUT/OSC_IN_12") (pintype "bidirectional"))
      (node (ref "X1") (pin "2") (pinfunction "2_2") (pintype "passive"))
    )
    (net (code "171") (name "Net-(U1D-PH1-OSC_OUT(PH1){slash}EVENTOUT{slash}OSC_OUT)") (class "Default")
      (node (ref "C3") (pin "2") (pinfunction "2_2") (pintype "passive"))
      (node (ref "R3") (pin "1") (pinfunction "1_1") (pintype "passive"))
      (node (ref "U1") (pin "13") (pinfunction "PH1-OSC_OUT(PH1)/EVENTOUT/OSC_OUT_13") (pintype "bidirectional"))
      (node (ref "X1") (pin "1") (pinfunction "1_1") (pintype "passive"))
    )
    (net (code "172") (name "Net-(U1D-VCAP_1)") (class "Default")
      (node (ref "C5") (pin "2") (pinfunction "2_2") (pintype "passive"))
      (node (ref "U1") (pin "49") (pinfunction "VCAP_1_49") (pintype "power_in"))
    )
    (net (code "173") (name "Net-(U1D-VCAP_2)") (class "Default")
      (node (ref "C7") (pin "2") (pinfunction "2_2") (pintype "passive"))
      (node (ref "U1") (pin "73") (pinfunction "VCAP_2_73") (pintype "power_in"))
    )
    (net (code "174") (name "Net-(U1E-VDDA)") (class "Default")
      (node (ref "C47") (pin "1") (pinfunction "1_1") (pintype "passive"))
      (node (ref "C48") (pin "1") (pinfunction "1_1") (pintype "passive"))
      (node (ref "L1") (pin "2") (pinfunction "2_2") (pintype "passive"))
      (node (ref "U1") (pin "22") (pinfunction "VDDA_22") (pintype "power_in"))
    )
    (net (code "175") (name "Net-(U3-FB)") (class "Default")
      (node (ref "R20") (pin "2") (pinfunction "2_2") (pintype "passive"))
      (node (ref "R23") (pin "1") (pinfunction "1_1") (pintype "passive"))
      (node (ref "U3") (pin "3") (pinfunction "FB_3") (pintype "passive"))
    )
    (net (code "176") (name "Net-(U5-Vin)") (class "Default")
      (node (ref "C18") (pin "2") (pinfunction "2_2") (pintype "passive"))
      (node (ref "R27") (pin "1") (pinfunction "1_1") (pintype "passive"))
      (node (ref "U5") (pin "2") (pinfunction "Vin_2") (pintype "passive"))
    )
    (net (code "177") (name "Net-(USB1-D+)") (class "Default")
      (node (ref "R6") (pin "2") (pinfunction "2_2") (pintype "passive"))
      (node (ref "R9") (pin "1") (pinfunction "1_1") (pintype "passive"))
      (node (ref "U6") (pin "4") (pinfunction "4_4") (pintype "passive"))
      (node (ref "USB1") (pin "3") (pinfunction "D+_3") (pintype "passive"))
    )
    (net (code "178") (name "Net-(USB1-D-)") (class "Default")
      (node (ref "R7") (pin "2") (pinfunction "2_2") (pintype "passive"))
      (node (ref "U6") (pin "6") (pinfunction "6_6") (pintype "passive"))
      (node (ref "USB1") (pin "2") (pinfunction "D-_2") (pintype "passive"))
    )
    (net (code "179") (name "Net-(USB1-VBUS)") (class "Default")
      (node (ref "L6") (pin "3") (pinfunction "3_3") (pintype "passive"))
      (node (ref "USB1") (pin "1") (pinfunction "VBUS_1") (pintype "passive"))
    )
    (net (code "180") (name "Vdd") (class "Default")
      (node (ref "C30") (pin "1") (pinfunction "1_1") (pintype "passive"))
      (node (ref "C31") (pin "2") (pinfunction "2_2") (pintype "passive"))
      (node (ref "C50") (pin "2") (pinfunction "2_2") (pintype "passive"))
      (node (ref "Q11") (pin "3") (pinfunction "E_3") (pintype "passive"))
      (node (ref "Q13") (pin "2") (pinfunction "D_2") (pintype "passive"))
      (node (ref "R45") (pin "2") (pinfunction "2_2") (pintype "passive"))
      (node (ref "R46") (pin "2") (pinfunction "2_2") (pintype "passive"))
      (node (ref "R47") (pin "1") (pinfunction "1_1") (pintype "passive"))
    )
    (net (code "181") (name "Vpp") (class "Default")
      (node (ref "C36") (pin "1") (pinfunction "1_1") (pintype "passive"))
      (node (ref "C37") (pin "2") (pinfunction "2_2") (pintype "passive"))
      (node (ref "C51") (pin "2") (pinfunction "2_2") (pintype "passive"))
      (node (ref "Q17") (pin "3") (pinfunction "E_3") (pintype "passive"))
      (node (ref "Q18") (pin "2") (pinfunction "D_2") (pintype "passive"))
      (node (ref "R55") (pin "2") (pinfunction "2_2") (pintype "passive"))
      (node (ref "R56") (pin "2") (pinfunction "2_2") (pintype "passive"))
      (node (ref "R60") (pin "1") (pinfunction "1_1") (pintype "passive"))
    )
    (net (code "182") (name "unconnected-(IC4-A8-Pad9)") (class "Default")
      (node (ref "IC4") (pin "9") (pinfunction "A8_9") (pintype "passive"))
    )
    (net (code "183") (name "unconnected-(IC4-B8-Pad12)") (class "Default")
      (node (ref "IC4") (pin "12") (pinfunction "B8_12") (pintype "passive"))
    )
    (net (code "184") (name "unconnected-(J1-Pad2)") (class "Default")
      (node (ref "J1") (pin "2") (pinfunction "2_2") (pintype "passive"))
    )
    (net (code "185") (name "unconnected-(J1-Pad11)") (class "Default")
      (node (ref "J1") (pin "11") (pinfunction "11_11") (pintype "passive"))
    )
    (net (code "186") (name "unconnected-(RP4-Pad4)") (class "Default")
      (node (ref "RP4") (pin "4") (pinfunction "4_4") (pintype "passive"))
    )
    (net (code "187") (name "unconnected-(RP4-Pad5)") (class "Default")
      (node (ref "RP4") (pin "5") (pinfunction "5_5") (pintype "passive"))
    )
    (net (code "188") (name "unconnected-(RP6-Pad8)") (class "Default")
      (node (ref "RP6") (pin "8") (pinfunction "8_8") (pintype "passive"))
    )
    (net (code "189") (name "unconnected-(RP7-Pad4)") (class "Default")
      (node (ref "RP7") (pin "4") (pinfunction "4_4") (pintype "passive"))
    )
    (net (code "190") (name "unconnected-(RP7-Pad5)") (class "Default")
      (node (ref "RP7") (pin "5") (pinfunction "5_5") (pintype "passive"))
    )
    (net (code "191") (name "unconnected-(RP8-Pad1)") (class "Default")
      (node (ref "RP8") (pin "1") (pinfunction "1_1") (pintype "passive"))
    )
    (net (code "192") (name "unconnected-(RP8-Pad8)") (class "Default")
      (node (ref "RP8") (pin "8") (pinfunction "8_8") (pintype "passive"))
    )
    (net (code "193") (name "unconnected-(U1B-PC15-OSC32_OUT(PC15){slash}EVENTOUT{slash}OSC32_OUT-Pad9)") (class "Default")
      (node (ref "U1") (pin "9") (pinfunction "PC15-OSC32_OUT(PC15)/EVENTOUT/OSC32_OUT_9") (pintype "bidirectional"))
    )
    (net (code "194") (name "unconnected-(U1B-PD4{slash}FSMC_NOE{slash}USART2_RTS{slash}EVENTOUT-Pad85)") (class "Default")
      (node (ref "U1") (pin "85") (pinfunction "PD4/FSMC_NOE/USART2_RTS/EVENTOUT_85") (pintype "bidirectional"))
    )
    (net (code "195") (name "unconnected-(U1B-PD10{slash}FSMC_D15{slash}USART3_CK{slash}EVENTOUT-Pad57)") (class "Default")
      (node (ref "U1") (pin "57") (pinfunction "PD10/FSMC_D15/USART3_CK/EVENTOUT_57") (pintype "bidirectional"))
    )
    (net (code "196") (name "unconnected-(U1C-PE0{slash}TIM4_ETR{slash}FSMC_NBL0{slash}DCMI_D2{slash}EVENTOUT-Pad97)") (class "Default")
      (node (ref "U1") (pin "97") (pinfunction "PE0/TIM4_ETR/FSMC_NBL0/DCMI_D2/EVENTOUT_97") (pintype "bidirectional"))
    )
    (net (code "197") (name "unconnected-(U1C-PE9{slash}FSMC_D6{slash}TIM1_CH1{slash}EVENTOUT-Pad40)") (class "Default")
      (node (ref "U1") (pin "40") (pinfunction "PE9/FSMC_D6/TIM1_CH1/EVENTOUT_40") (pintype "bidirectional"))
    )
    (net (code "198") (name "unconnected-(U1C-PE10{slash}FSMC_D7{slash}TIM1_CH2N{slash}EVENTOUT-Pad41)") (class "Default")
      (node (ref "U1") (pin "41") (pinfunction "PE10/FSMC_D7/TIM1_CH2N/EVENTOUT_41") (pintype "bidirectional"))
    )
    (net (code "199") (name "unconnected-(U1C-PE11{slash}FSMC_D8{slash}TIM1_CH2{slash}EVENTOUT-Pad42)") (class "Default")
      (node (ref "U1") (pin "42") (pinfunction "PE11/FSMC_D8/TIM1_CH2/EVENTOUT_42") (pintype "bidirectional"))
    )
    (net (code "200") (name "unconnected-(U1C-PE12{slash}FSMC_D9{slash}TIM1_CH3N{slash}EVENTOUT-Pad43)") (class "Default")
      (node (ref "U1") (pin "43") (pinfunction "PE12/FSMC_D9/TIM1_CH3N/EVENTOUT_43") (pintype "bidirectional"))
    )
    (net (code "201") (name "unconnected-(U1C-PE13{slash}FSMC_D10{slash}TIM1_CH3{slash}EVENTOUT-Pad44)") (class "Default")
      (node (ref "U1") (pin "44") (pinfunction "PE13/FSMC_D10/TIM1_CH3/EVENTOUT_44") (pintype "bidirectional"))
    )
    (net (code "202") (name "unconnected-(U1C-PE14{slash}FSMC_D11{slash}TIM1_CH4{slash}EVENTOUT-Pad45)") (class "Default")
      (node (ref "U1") (pin "45") (pinfunction "PE14/FSMC_D11/TIM1_CH4/EVENTOUT_45") (pintype "bidirectional"))
    )
    (net (code "203") (name "unconnected-(U1C-PE15{slash}FSMC_D12{slash}TIM1_BKIN{slash}EVENTOUT-Pad46)") (class "Default")
      (node (ref "U1") (pin "46") (pinfunction "PE15/FSMC_D12/TIM1_BKIN/EVENTOUT_46") (pintype "bidirectional"))
    )
    (net (code "204") (name "unconnected-(U5-TEMP-Pad3)") (class "Default")
      (node (ref "U5") (pin "3") (pinfunction "TEMP_3") (pintype "passive"))
    )
    (net (code "205") (name "unconnected-(U5-TP-Pad1)") (class "Default")
      (node (ref "U5") (pin "1") (pinfunction "TP_1") (pintype "passive"))
    )
    (net (code "206") (name "unconnected-(U5-TP-Pad7)") (class "Default")
      (node (ref "U5") (pin "7") (pinfunction "TP_7") (pintype "passive"))
    )
    (net (code "207") (name "unconnected-(U5-TP-Pad8)") (class "Default")
      (node (ref "U5") (pin "8") (pinfunction "TP_8") (pintype "passive"))
    )
    (net (code "208") (name "unconnected-(U5-Trim-Pad5)") (class "Default")
      (node (ref "U5") (pin "5") (pinfunction "Trim_5") (pintype "passive"))
    )
    (net (code "209") (name "unconnected-(U6-+-Pad5)") (class "Default")
      (node (ref "U6") (pin "5") (pinfunction "+_5") (pintype "passive"))
    )
    (net (code "210") (name "unconnected-(U6-Pad1)") (class "Default")
      (node (ref "U6") (pin "1") (pinfunction "1_1") (pintype "passive"))
    )
    (net (code "211") (name "unconnected-(U6-Pad3)") (class "Default")
      (node (ref "U6") (pin "3") (pinfunction "3_3") (pintype "passive"))
    )
    (net (code "212") (name "unconnected-(U7-+-Pad5)") (class "Default")
      (node (ref "U7") (pin "5") (pinfunction "+_5") (pintype "passive"))
    )
    (net (code "213") (name "unconnected-(U8-+-Pad5)") (class "Default")
      (node (ref "U8") (pin "5") (pinfunction "+_5") (pintype "passive"))
    )
    (net (code "214") (name "unconnected-(U9-+-Pad5)") (class "Default")
      (node (ref "U9") (pin "5") (pinfunction "+_5") (pintype "passive"))
    )
    (net (code "215") (name "unconnected-(U10-+-Pad5)") (class "Default")
      (node (ref "U10") (pin "5") (pinfunction "+_5") (pintype "passive"))
    )
    (net (code "216") (name "unconnected-(U10-Pad1)") (class "Default")
      (node (ref "U10") (pin "1") (pinfunction "1_1") (pintype "passive"))
    )
    (net (code "217") (name "unconnected-(U10-Pad3)") (class "Default")
      (node (ref "U10") (pin "3") (pinfunction "3_3") (pintype "passive"))
    )
    (net (code "218") (name "unconnected-(U11-+-Pad5)") (class "Default")
      (node (ref "U11") (pin "5") (pinfunction "+_5") (pintype "passive"))
    )
  )
)
